# customESC.net
KiCad netlist of a schematic drawn in EAGLE
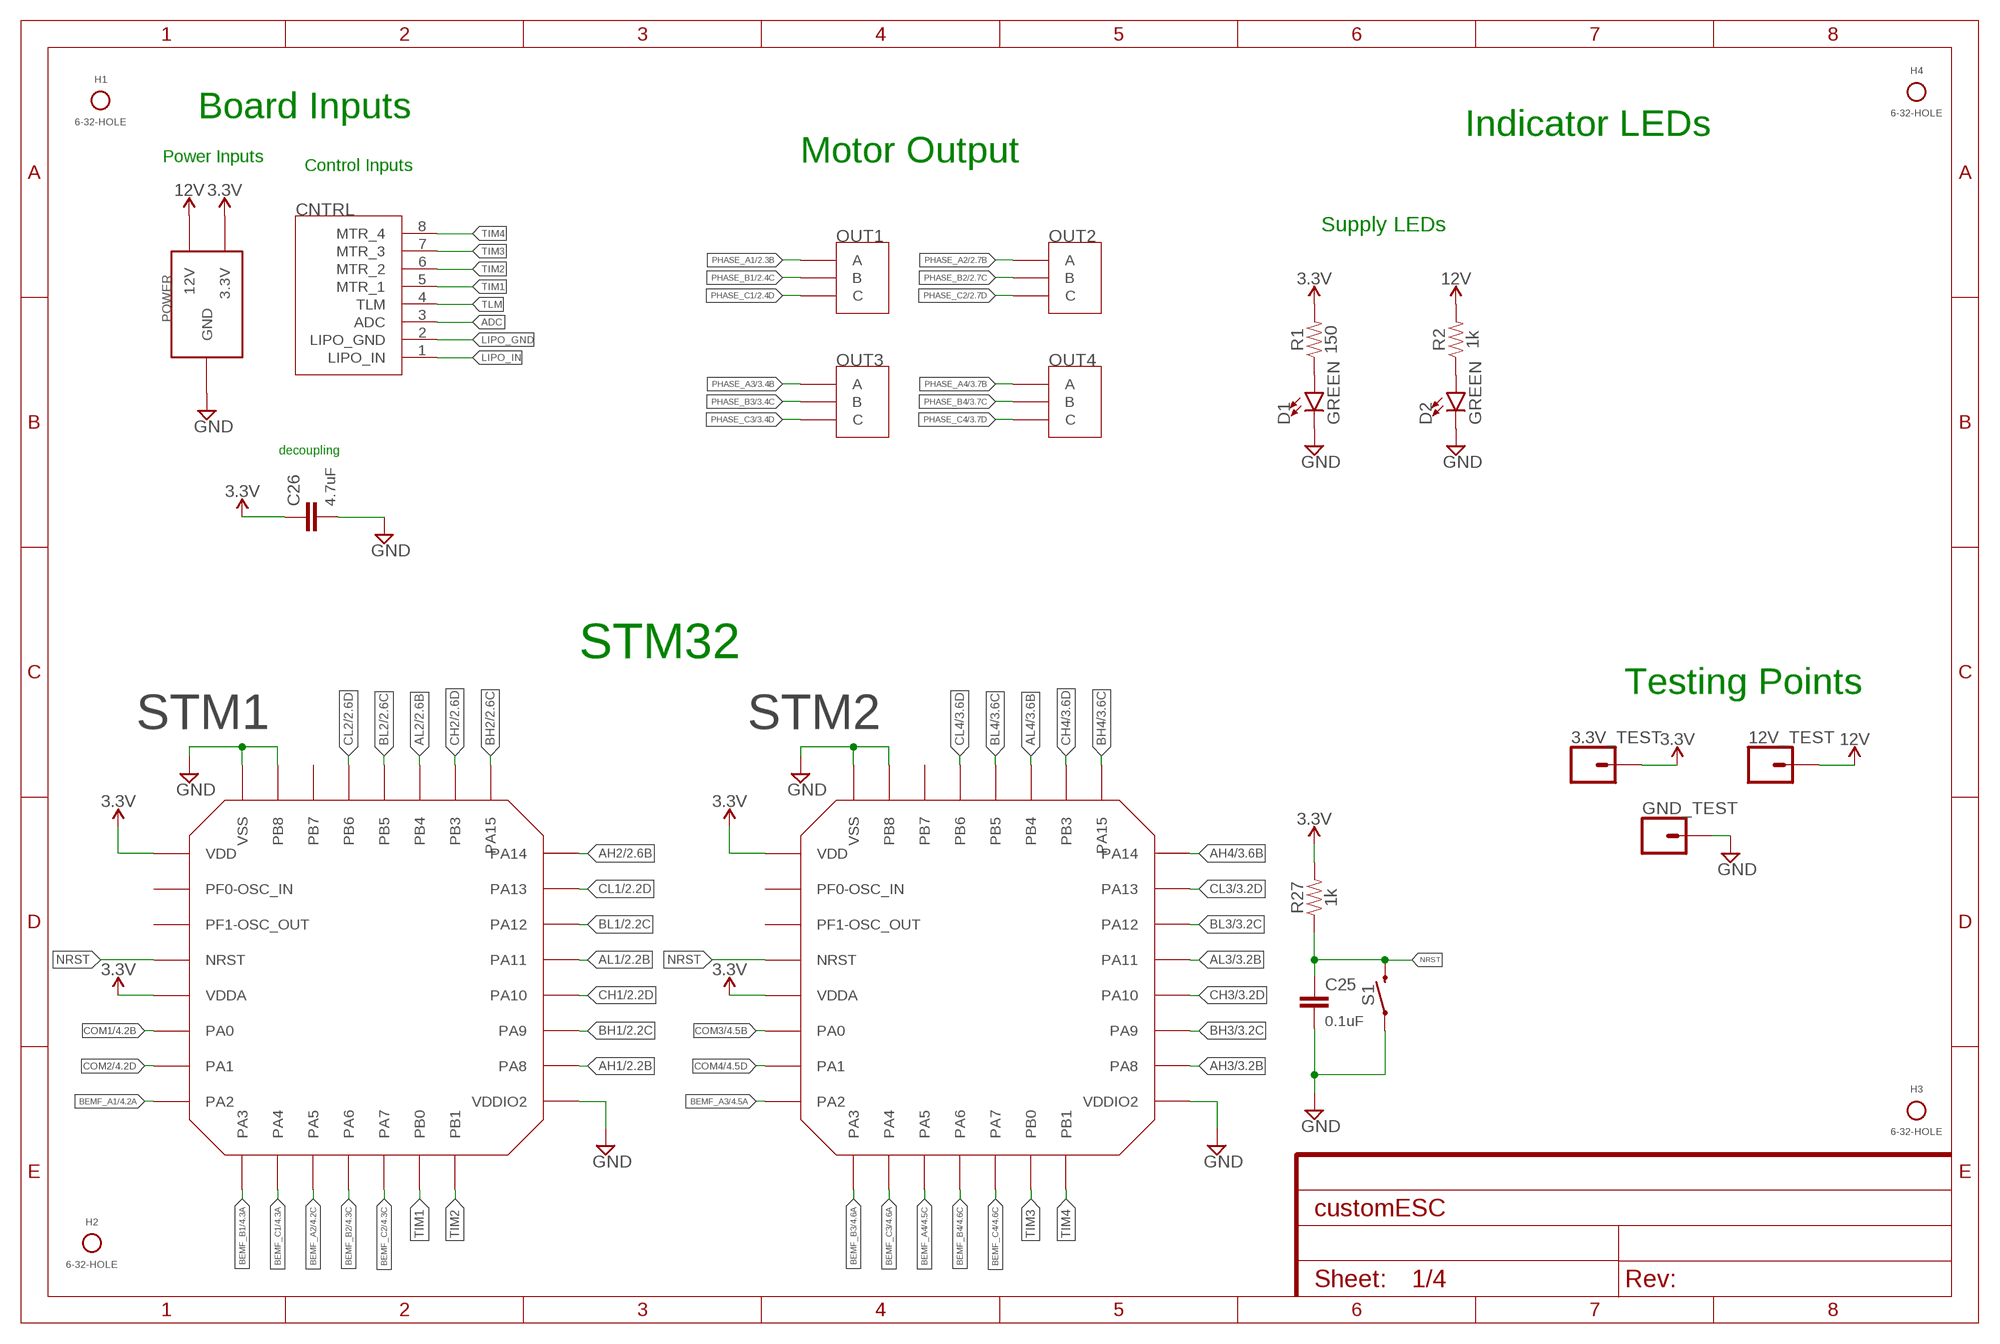
[diagram p0: schematic, sheet 1]
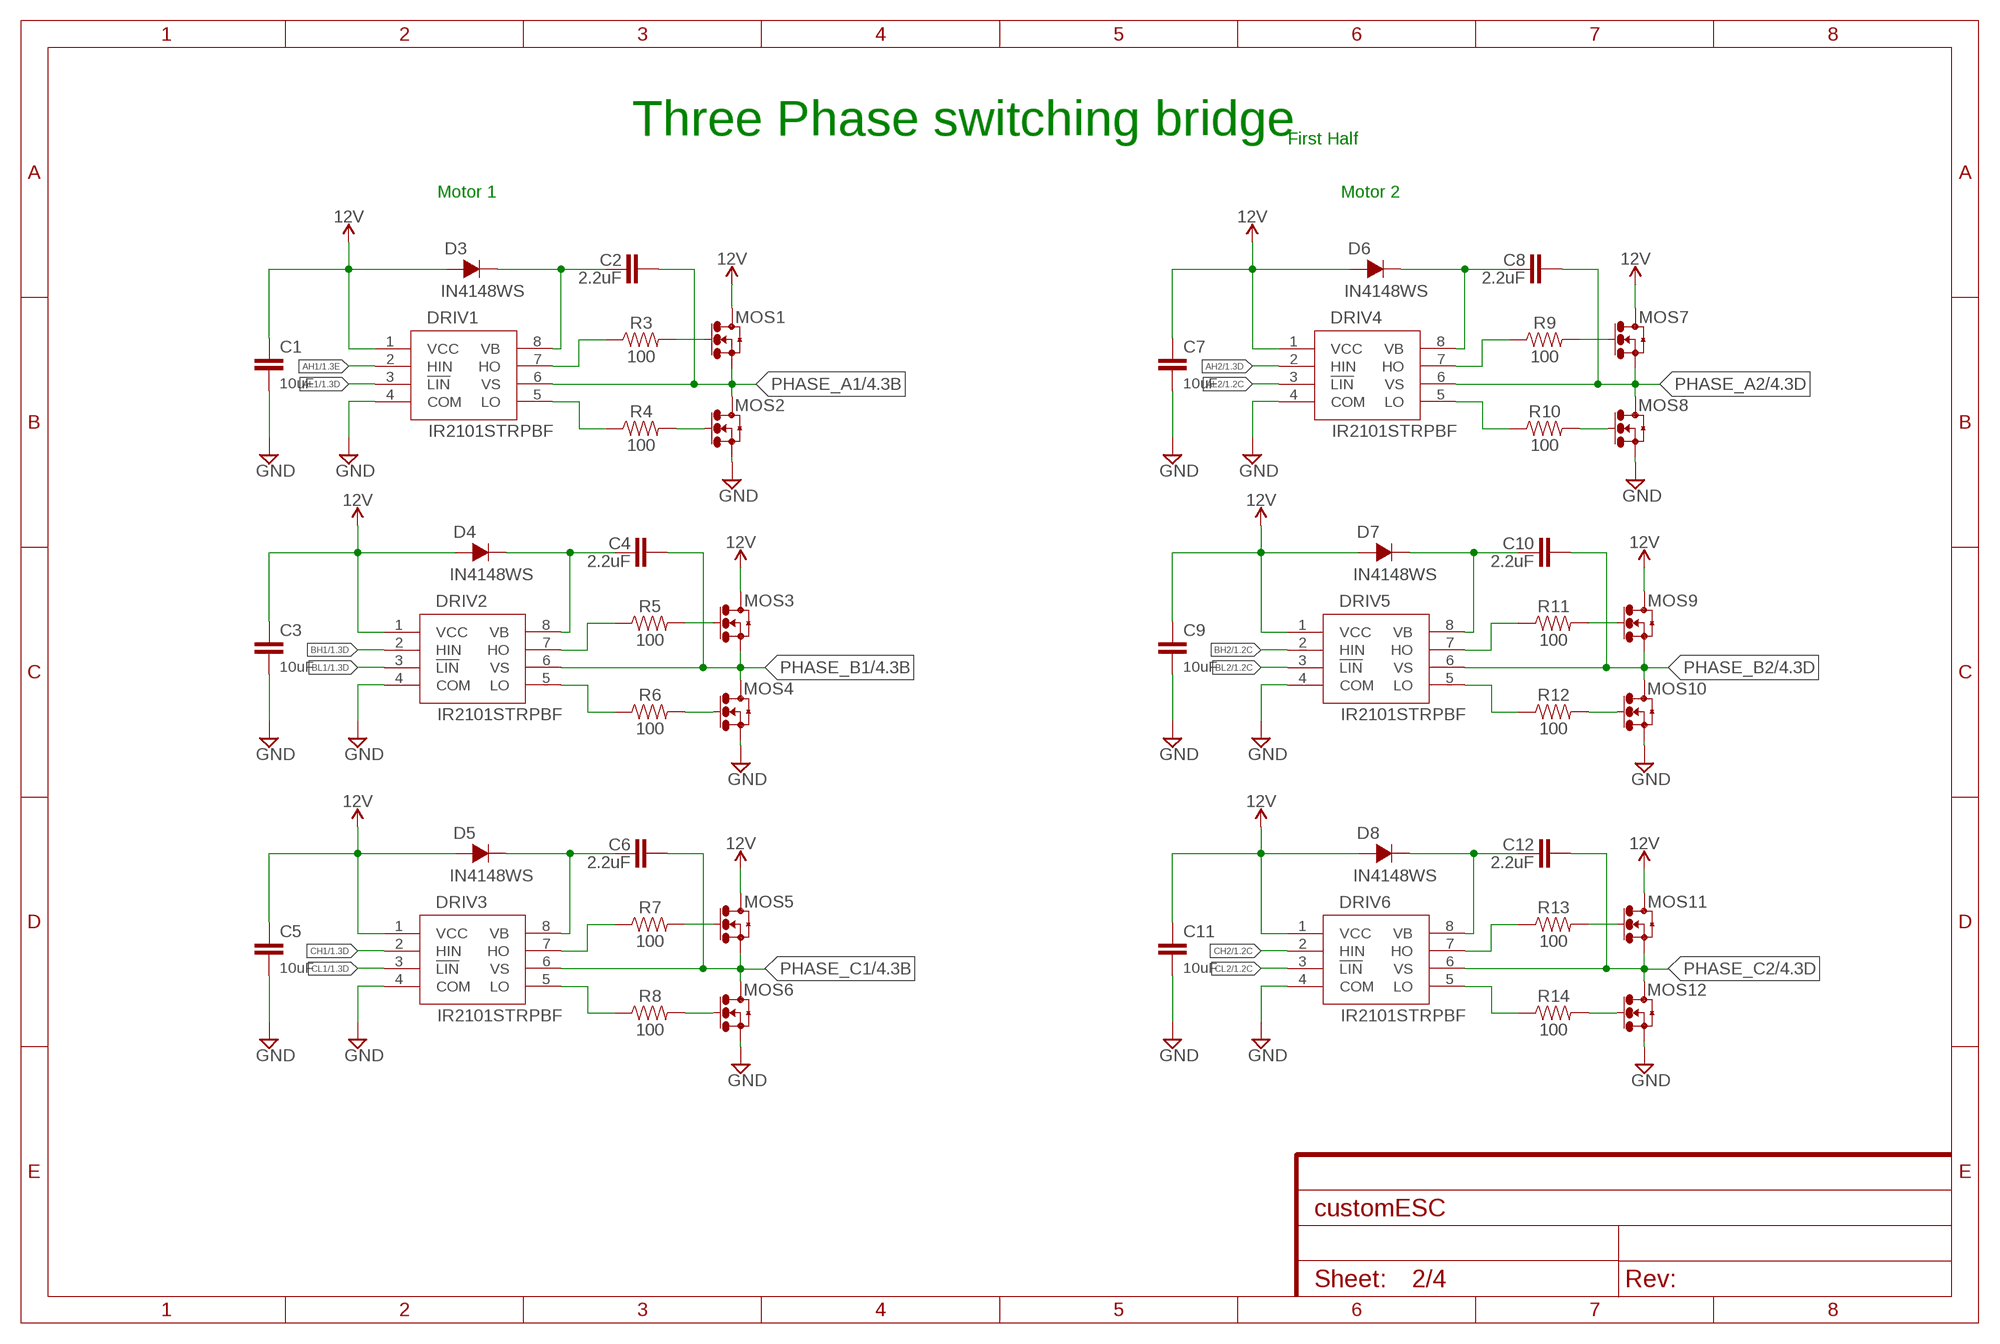
[diagram p1: schematic, sheet 2]
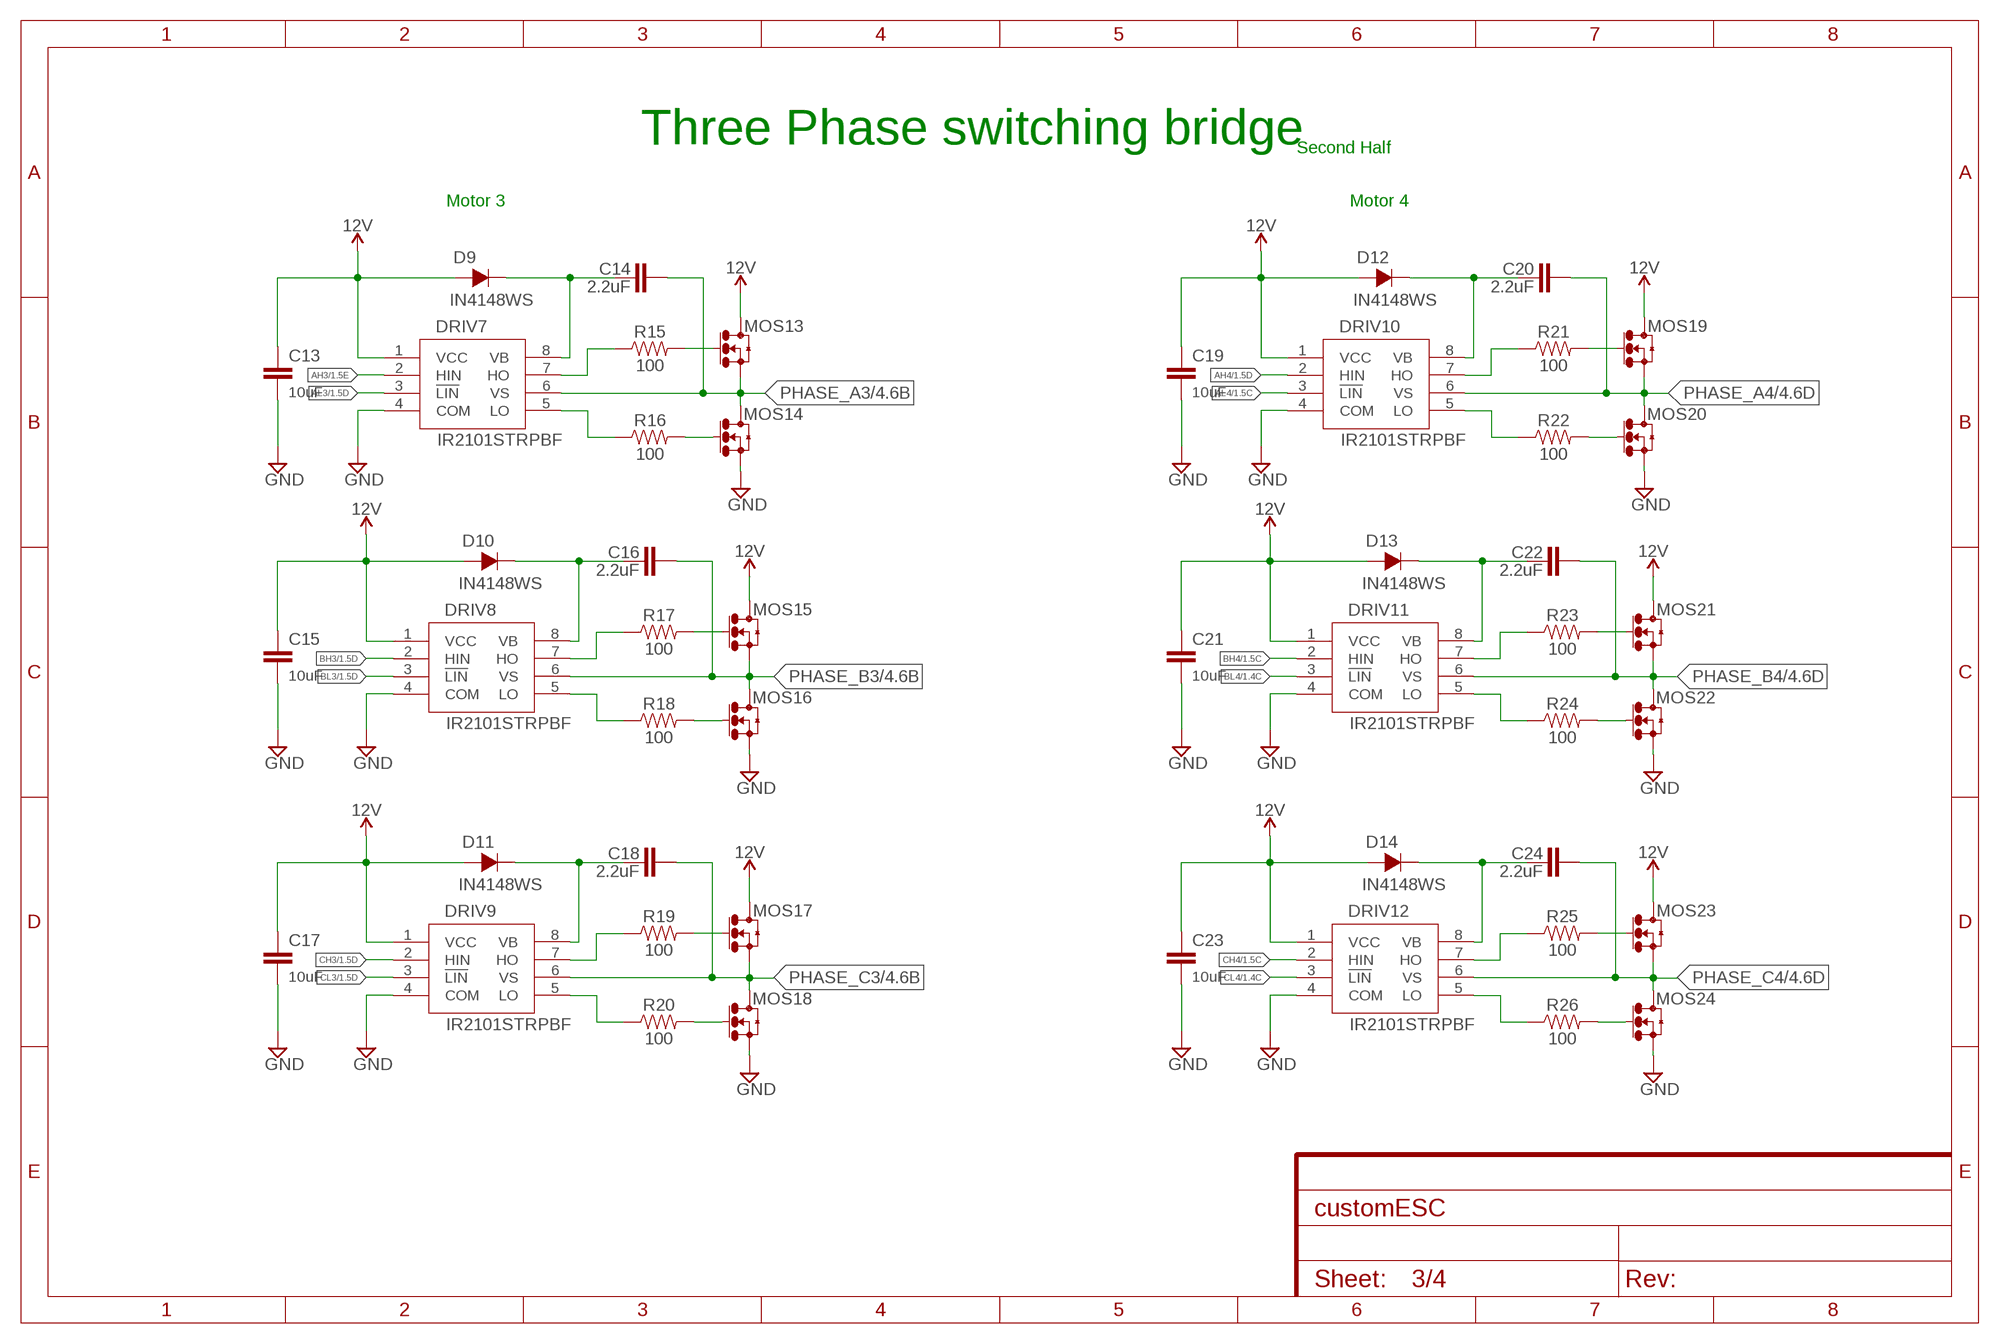
[diagram p2: schematic, sheet 3]
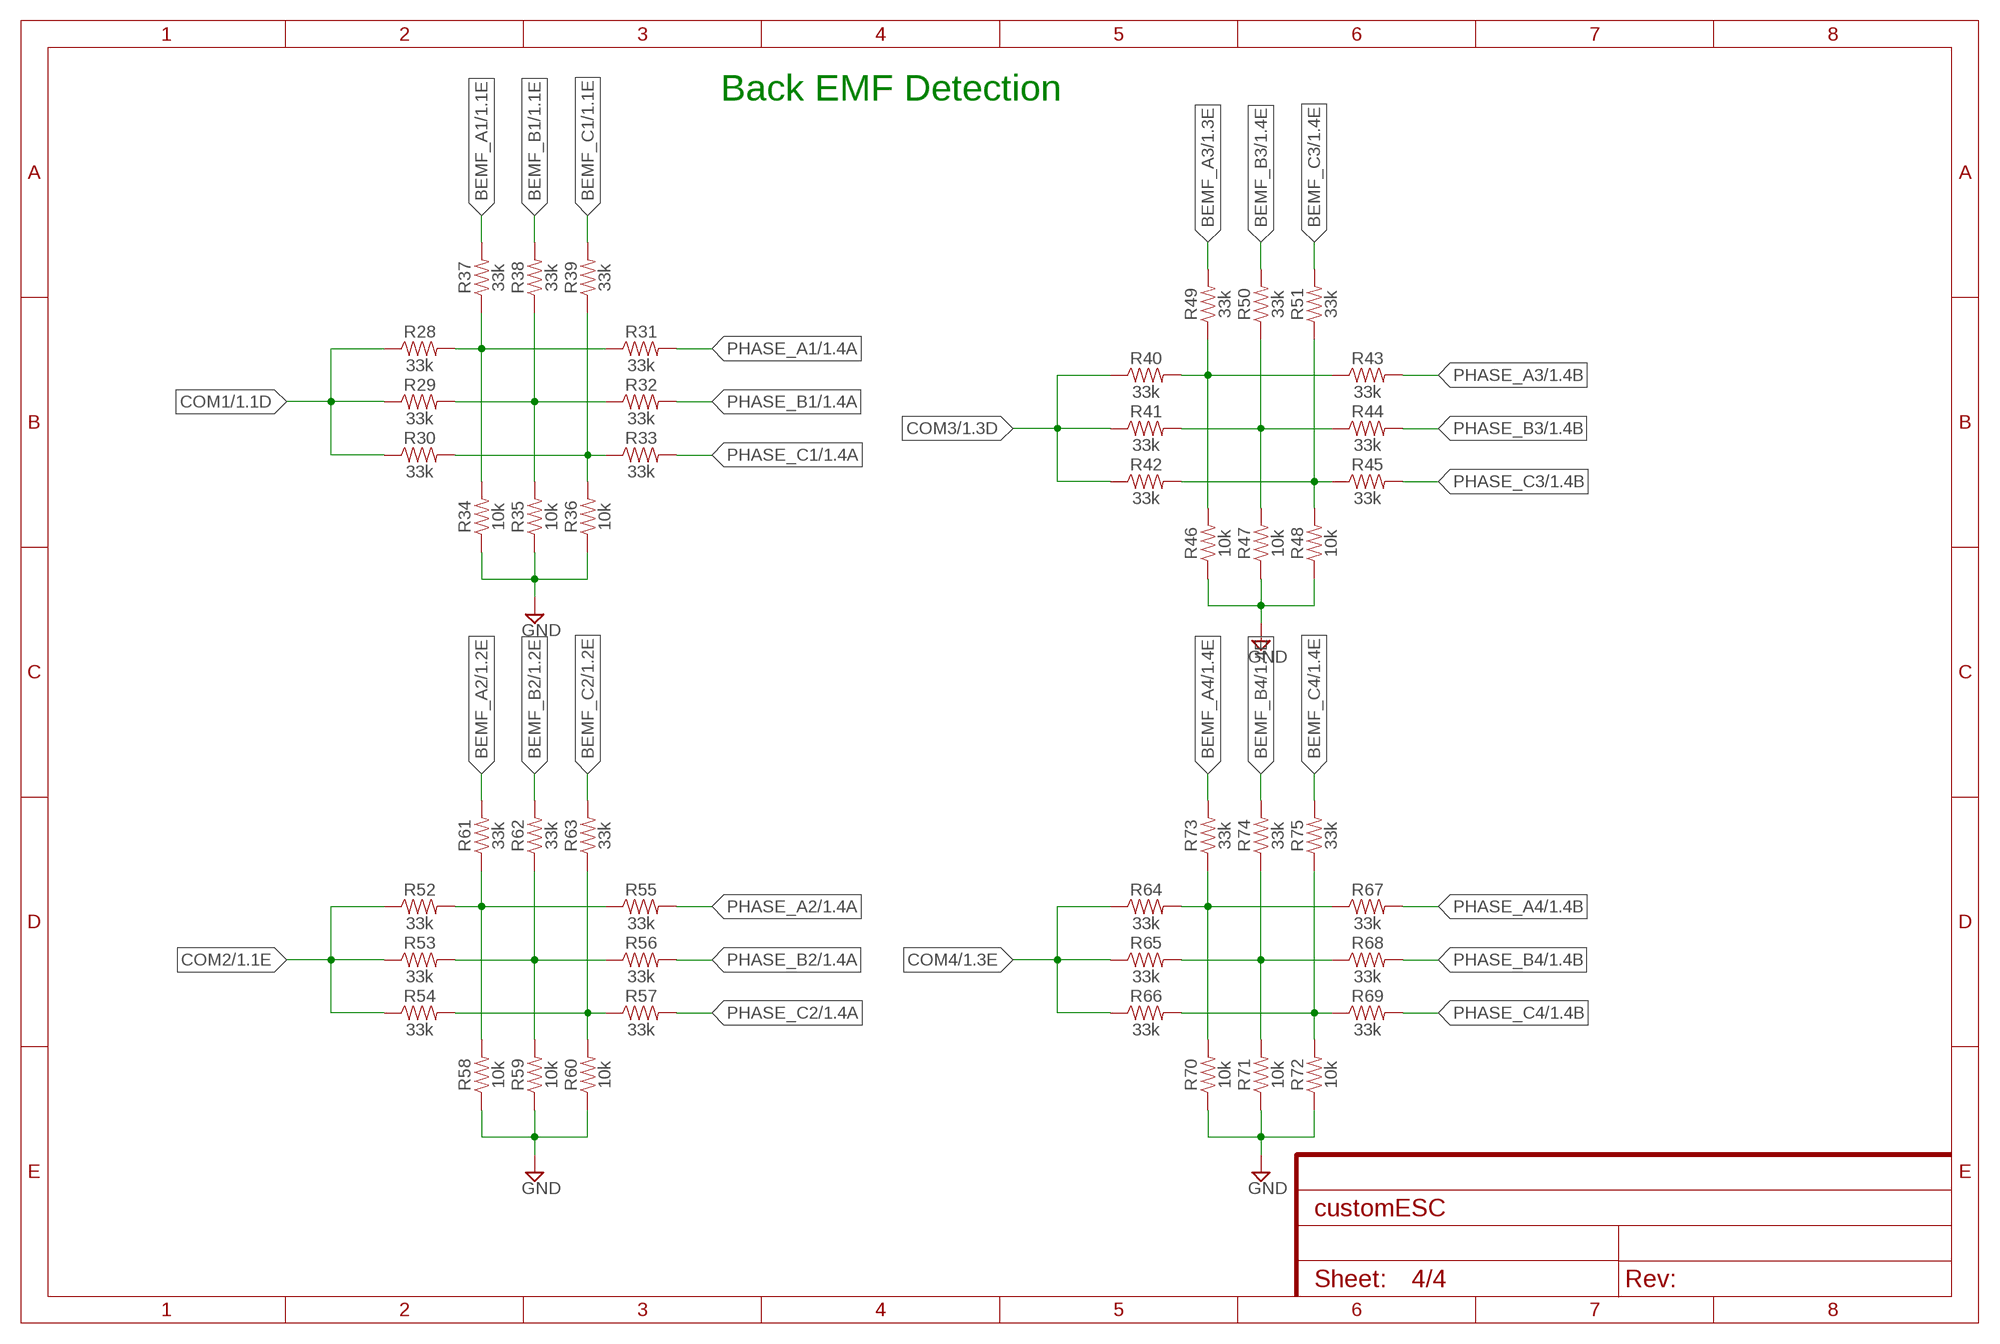
[diagram p3: schematic, sheet 4]

(export (version "E")
  (design (tool "Eeschema 10.0.6"))
  (components
    (comp (ref "R28")
      (value "33k")
      (footprint "eagle-import:0603")
      (libsource (lib "eagle-import") (part "1KOHM-0603-1/10W-1%"))
    )
    (comp (ref "R29")
      (value "33k")
      (footprint "eagle-import:0603")
      (libsource (lib "eagle-import") (part "1KOHM-0603-1/10W-1%"))
    )
    (comp (ref "R30")
      (value "33k")
      (footprint "eagle-import:0603")
      (libsource (lib "eagle-import") (part "1KOHM-0603-1/10W-1%"))
    )
    (comp (ref "R31")
      (value "33k")
      (footprint "eagle-import:0603")
      (libsource (lib "eagle-import") (part "1KOHM-0603-1/10W-1%"))
    )
    (comp (ref "R32")
      (value "33k")
      (footprint "eagle-import:0603")
      (libsource (lib "eagle-import") (part "1KOHM-0603-1/10W-1%"))
    )
    (comp (ref "R33")
      (value "33k")
      (footprint "eagle-import:0603")
      (libsource (lib "eagle-import") (part "1KOHM-0603-1/10W-1%"))
    )
    (comp (ref "R34")
      (value "10k")
      (footprint "eagle-import:0603")
      (libsource (lib "eagle-import") (part "1KOHM-0603-1/10W-1%"))
    )
    (comp (ref "R35")
      (value "10k")
      (footprint "eagle-import:0603")
      (libsource (lib "eagle-import") (part "1KOHM-0603-1/10W-1%"))
    )
    (comp (ref "R36")
      (value "10k")
      (footprint "eagle-import:0603")
      (libsource (lib "eagle-import") (part "1KOHM-0603-1/10W-1%"))
    )
    (comp (ref "R37")
      (value "33k")
      (footprint "eagle-import:0603")
      (libsource (lib "eagle-import") (part "1KOHM-0603-1/10W-1%"))
    )
    (comp (ref "R38")
      (value "33k")
      (footprint "eagle-import:0603")
      (libsource (lib "eagle-import") (part "1KOHM-0603-1/10W-1%"))
    )
    (comp (ref "R39")
      (value "33k")
      (footprint "eagle-import:0603")
      (libsource (lib "eagle-import") (part "1KOHM-0603-1/10W-1%"))
    )
    (comp (ref "R40")
      (value "33k")
      (footprint "eagle-import:0603")
      (libsource (lib "eagle-import") (part "1KOHM-0603-1/10W-1%"))
    )
    (comp (ref "R41")
      (value "33k")
      (footprint "eagle-import:0603")
      (libsource (lib "eagle-import") (part "1KOHM-0603-1/10W-1%"))
    )
    (comp (ref "R42")
      (value "33k")
      (footprint "eagle-import:0603")
      (libsource (lib "eagle-import") (part "1KOHM-0603-1/10W-1%"))
    )
    (comp (ref "R43")
      (value "33k")
      (footprint "eagle-import:0603")
      (libsource (lib "eagle-import") (part "1KOHM-0603-1/10W-1%"))
    )
    (comp (ref "R44")
      (value "33k")
      (footprint "eagle-import:0603")
      (libsource (lib "eagle-import") (part "1KOHM-0603-1/10W-1%"))
    )
    (comp (ref "R45")
      (value "33k")
      (footprint "eagle-import:0603")
      (libsource (lib "eagle-import") (part "1KOHM-0603-1/10W-1%"))
    )
    (comp (ref "R46")
      (value "10k")
      (footprint "eagle-import:0603")
      (libsource (lib "eagle-import") (part "1KOHM-0603-1/10W-1%"))
    )
    (comp (ref "R47")
      (value "10k")
      (footprint "eagle-import:0603")
      (libsource (lib "eagle-import") (part "1KOHM-0603-1/10W-1%"))
    )
    (comp (ref "R48")
      (value "10k")
      (footprint "eagle-import:0603")
      (libsource (lib "eagle-import") (part "1KOHM-0603-1/10W-1%"))
    )
    (comp (ref "R49")
      (value "33k")
      (footprint "eagle-import:0603")
      (libsource (lib "eagle-import") (part "1KOHM-0603-1/10W-1%"))
    )
    (comp (ref "R50")
      (value "33k")
      (footprint "eagle-import:0603")
      (libsource (lib "eagle-import") (part "1KOHM-0603-1/10W-1%"))
    )
    (comp (ref "R51")
      (value "33k")
      (footprint "eagle-import:0603")
      (libsource (lib "eagle-import") (part "1KOHM-0603-1/10W-1%"))
    )
    (comp (ref "R52")
      (value "33k")
      (footprint "eagle-import:0603")
      (libsource (lib "eagle-import") (part "1KOHM-0603-1/10W-1%"))
    )
    (comp (ref "R53")
      (value "33k")
      (footprint "eagle-import:0603")
      (libsource (lib "eagle-import") (part "1KOHM-0603-1/10W-1%"))
    )
    (comp (ref "R54")
      (value "33k")
      (footprint "eagle-import:0603")
      (libsource (lib "eagle-import") (part "1KOHM-0603-1/10W-1%"))
    )
    (comp (ref "R55")
      (value "33k")
      (footprint "eagle-import:0603")
      (libsource (lib "eagle-import") (part "1KOHM-0603-1/10W-1%"))
    )
    (comp (ref "R56")
      (value "33k")
      (footprint "eagle-import:0603")
      (libsource (lib "eagle-import") (part "1KOHM-0603-1/10W-1%"))
    )
    (comp (ref "R57")
      (value "33k")
      (footprint "eagle-import:0603")
      (libsource (lib "eagle-import") (part "1KOHM-0603-1/10W-1%"))
    )
    (comp (ref "R58")
      (value "10k")
      (footprint "eagle-import:0603")
      (libsource (lib "eagle-import") (part "1KOHM-0603-1/10W-1%"))
    )
    (comp (ref "R59")
      (value "10k")
      (footprint "eagle-import:0603")
      (libsource (lib "eagle-import") (part "1KOHM-0603-1/10W-1%"))
    )
    (comp (ref "R60")
      (value "10k")
      (footprint "eagle-import:0603")
      (libsource (lib "eagle-import") (part "1KOHM-0603-1/10W-1%"))
    )
    (comp (ref "R61")
      (value "33k")
      (footprint "eagle-import:0603")
      (libsource (lib "eagle-import") (part "1KOHM-0603-1/10W-1%"))
    )
    (comp (ref "R62")
      (value "33k")
      (footprint "eagle-import:0603")
      (libsource (lib "eagle-import") (part "1KOHM-0603-1/10W-1%"))
    )
    (comp (ref "R63")
      (value "33k")
      (footprint "eagle-import:0603")
      (libsource (lib "eagle-import") (part "1KOHM-0603-1/10W-1%"))
    )
    (comp (ref "R64")
      (value "33k")
      (footprint "eagle-import:0603")
      (libsource (lib "eagle-import") (part "1KOHM-0603-1/10W-1%"))
    )
    (comp (ref "R65")
      (value "33k")
      (footprint "eagle-import:0603")
      (libsource (lib "eagle-import") (part "1KOHM-0603-1/10W-1%"))
    )
    (comp (ref "R66")
      (value "33k")
      (footprint "eagle-import:0603")
      (libsource (lib "eagle-import") (part "1KOHM-0603-1/10W-1%"))
    )
    (comp (ref "R67")
      (value "33k")
      (footprint "eagle-import:0603")
      (libsource (lib "eagle-import") (part "1KOHM-0603-1/10W-1%"))
    )
    (comp (ref "R68")
      (value "33k")
      (footprint "eagle-import:0603")
      (libsource (lib "eagle-import") (part "1KOHM-0603-1/10W-1%"))
    )
    (comp (ref "R69")
      (value "33k")
      (footprint "eagle-import:0603")
      (libsource (lib "eagle-import") (part "1KOHM-0603-1/10W-1%"))
    )
    (comp (ref "R70")
      (value "10k")
      (footprint "eagle-import:0603")
      (libsource (lib "eagle-import") (part "1KOHM-0603-1/10W-1%"))
    )
    (comp (ref "R71")
      (value "10k")
      (footprint "eagle-import:0603")
      (libsource (lib "eagle-import") (part "1KOHM-0603-1/10W-1%"))
    )
    (comp (ref "R72")
      (value "10k")
      (footprint "eagle-import:0603")
      (libsource (lib "eagle-import") (part "1KOHM-0603-1/10W-1%"))
    )
    (comp (ref "R73")
      (value "33k")
      (footprint "eagle-import:0603")
      (libsource (lib "eagle-import") (part "1KOHM-0603-1/10W-1%"))
    )
    (comp (ref "R74")
      (value "33k")
      (footprint "eagle-import:0603")
      (libsource (lib "eagle-import") (part "1KOHM-0603-1/10W-1%"))
    )
    (comp (ref "R75")
      (value "33k")
      (footprint "eagle-import:0603")
      (libsource (lib "eagle-import") (part "1KOHM-0603-1/10W-1%"))
    )
    (comp (ref "3.3V_TEST")
      (value "CONN_01")
      (footprint "eagle-import:1X01")
      (libsource (lib "eagle-import") (part "CONN_01"))
    )
    (comp (ref "12V_TEST")
      (value "CONN_01")
      (footprint "eagle-import:1X01")
      (libsource (lib "eagle-import") (part "CONN_01"))
    )
    (comp (ref "C25")
      (value "0.1uF")
      (footprint "eagle-import:0603")
      (libsource (lib "eagle-import") (part "10UF-0603-6.3V-20%"))
    )
    (comp (ref "C26")
      (value "4.7uF")
      (footprint "eagle-import:0603")
      (libsource (lib "eagle-import") (part "10UF-0603-6.3V-20%"))
    )
    (comp (ref "CNTRL")
      (value "JST_8_PIN")
      (footprint "eagle-import:JST_8_PIN")
      (libsource (lib "eagle-import") (part "JST_8_PIN"))
    )
    (comp (ref "D1")
      (value "GREEN")
      (footprint "eagle-import:LED-0603")
      (libsource (lib "eagle-import") (part "LED-GREEN0603"))
    )
    (comp (ref "D2")
      (value "GREEN")
      (footprint "eagle-import:LED-0603")
      (libsource (lib "eagle-import") (part "LED-GREEN0603"))
    )
    (comp (ref "GND_TEST")
      (value "CONN_01")
      (footprint "eagle-import:1X01")
      (libsource (lib "eagle-import") (part "CONN_01"))
    )
    (comp (ref "H1")
      (value "6-32-HOLE")
      (footprint "eagle-import:MOUNTING_HOLE")
      (libsource (lib "eagle-import") (part "6-32-HOLE"))
    )
    (comp (ref "H2")
      (value "6-32-HOLE")
      (footprint "eagle-import:MOUNTING_HOLE")
      (libsource (lib "eagle-import") (part "6-32-HOLE"))
    )
    (comp (ref "H3")
      (value "6-32-HOLE")
      (footprint "eagle-import:MOUNTING_HOLE")
      (libsource (lib "eagle-import") (part "6-32-HOLE"))
    )
    (comp (ref "H4")
      (value "6-32-HOLE")
      (footprint "eagle-import:MOUNTING_HOLE")
      (libsource (lib "eagle-import") (part "6-32-HOLE"))
    )
    (comp (ref "OUT1")
      (value "IPBT-103-H1-T-S")
      (footprint "eagle-import:IPBT-103-H1-T-S")
      (libsource (lib "eagle-import") (part "IPBT-103-H1-T-S"))
    )
    (comp (ref "OUT2")
      (value "IPBT-103-H1-T-S")
      (footprint "eagle-import:IPBT-103-H1-T-S")
      (libsource (lib "eagle-import") (part "IPBT-103-H1-T-S"))
    )
    (comp (ref "OUT3")
      (value "IPBT-103-H1-T-S")
      (footprint "eagle-import:IPBT-103-H1-T-S")
      (libsource (lib "eagle-import") (part "IPBT-103-H1-T-S"))
    )
    (comp (ref "OUT4")
      (value "IPBT-103-H1-T-S")
      (footprint "eagle-import:IPBT-103-H1-T-S")
      (libsource (lib "eagle-import") (part "IPBT-103-H1-T-S"))
    )
    (comp (ref "POWER")
      (value "12V-CONNECTOR")
      (footprint "eagle-import:12V-CONNECTOR")
      (libsource (lib "eagle-import") (part "12V-CONNECTOR"))
    )
    (comp (ref "R1")
      (value "150")
      (footprint "eagle-import:0603")
      (libsource (lib "eagle-import") (part "1KOHM-0603-1/10W-1%"))
    )
    (comp (ref "R2")
      (value "1k")
      (footprint "eagle-import:0603")
      (libsource (lib "eagle-import") (part "1KOHM-0603-1/10W-1%"))
    )
    (comp (ref "R27")
      (value "1k")
      (footprint "eagle-import:0603")
      (libsource (lib "eagle-import") (part "1KOHM-0603-1/10W-1%"))
    )
    (comp (ref "S1")
      (value "MOMENTARY-SWITCH-SPST-SMD-6.0X3.5MM")
      (footprint "eagle-import:TACTILE_SWITCH_SMD_6.0X3.5MM")
      (libsource (lib "eagle-import") (part "MOMENTARY-SWITCH-SPST-SMD-6.0X3.5MM"))
    )
    (comp (ref "STM1")
      (value "STM32F042K6T6")
      (footprint "eagle-import:STM32F042K6T6")
      (libsource (lib "eagle-import") (part "STM32F042K6T6"))
    )
    (comp (ref "STM2")
      (value "STM32F042K6T6")
      (footprint "eagle-import:STM32F042K6T6")
      (libsource (lib "eagle-import") (part "STM32F042K6T6"))
    )
    (comp (ref "C13")
      (value "10uF")
      (footprint "eagle-import:0603")
      (libsource (lib "eagle-import") (part "10UF-0603-6.3V-20%"))
    )
    (comp (ref "C14")
      (value "2.2uF")
      (footprint "eagle-import:0603")
      (libsource (lib "eagle-import") (part "10UF-0603-6.3V-20%"))
    )
    (comp (ref "C15")
      (value "10uF")
      (footprint "eagle-import:0603")
      (libsource (lib "eagle-import") (part "10UF-0603-6.3V-20%"))
    )
    (comp (ref "C16")
      (value "2.2uF")
      (footprint "eagle-import:0603")
      (libsource (lib "eagle-import") (part "10UF-0603-6.3V-20%"))
    )
    (comp (ref "C17")
      (value "10uF")
      (footprint "eagle-import:0603")
      (libsource (lib "eagle-import") (part "10UF-0603-6.3V-20%"))
    )
    (comp (ref "C18")
      (value "2.2uF")
      (footprint "eagle-import:0603")
      (libsource (lib "eagle-import") (part "10UF-0603-6.3V-20%"))
    )
    (comp (ref "C19")
      (value "10uF")
      (footprint "eagle-import:0603")
      (libsource (lib "eagle-import") (part "10UF-0603-6.3V-20%"))
    )
    (comp (ref "C20")
      (value "2.2uF")
      (footprint "eagle-import:0603")
      (libsource (lib "eagle-import") (part "10UF-0603-6.3V-20%"))
    )
    (comp (ref "C21")
      (value "10uF")
      (footprint "eagle-import:0603")
      (libsource (lib "eagle-import") (part "10UF-0603-6.3V-20%"))
    )
    (comp (ref "C22")
      (value "2.2uF")
      (footprint "eagle-import:0603")
      (libsource (lib "eagle-import") (part "10UF-0603-6.3V-20%"))
    )
    (comp (ref "C23")
      (value "10uF")
      (footprint "eagle-import:0603")
      (libsource (lib "eagle-import") (part "10UF-0603-6.3V-20%"))
    )
    (comp (ref "C24")
      (value "2.2uF")
      (footprint "eagle-import:0603")
      (libsource (lib "eagle-import") (part "10UF-0603-6.3V-20%"))
    )
    (comp (ref "D9")
      (value "IN4148WS")
      (footprint "eagle-import:IN4148WS")
      (libsource (lib "eagle-import") (part "IN4148WS"))
    )
    (comp (ref "D10")
      (value "IN4148WS")
      (footprint "eagle-import:IN4148WS")
      (libsource (lib "eagle-import") (part "IN4148WS"))
    )
    (comp (ref "D11")
      (value "IN4148WS")
      (footprint "eagle-import:IN4148WS")
      (libsource (lib "eagle-import") (part "IN4148WS"))
    )
    (comp (ref "D12")
      (value "IN4148WS")
      (footprint "eagle-import:IN4148WS")
      (libsource (lib "eagle-import") (part "IN4148WS"))
    )
    (comp (ref "D13")
      (value "IN4148WS")
      (footprint "eagle-import:IN4148WS")
      (libsource (lib "eagle-import") (part "IN4148WS"))
    )
    (comp (ref "D14")
      (value "IN4148WS")
      (footprint "eagle-import:IN4148WS")
      (libsource (lib "eagle-import") (part "IN4148WS"))
    )
    (comp (ref "DRIV7")
      (value "IR2101STRPBF")
      (footprint "eagle-import:IR2101STRPBF")
      (libsource (lib "eagle-import") (part "IR2101STRPBF"))
    )
    (comp (ref "DRIV8")
      (value "IR2101STRPBF")
      (footprint "eagle-import:IR2101STRPBF")
      (libsource (lib "eagle-import") (part "IR2101STRPBF"))
    )
    (comp (ref "DRIV9")
      (value "IR2101STRPBF")
      (footprint "eagle-import:IR2101STRPBF")
      (libsource (lib "eagle-import") (part "IR2101STRPBF"))
    )
    (comp (ref "DRIV10")
      (value "IR2101STRPBF")
      (footprint "eagle-import:IR2101STRPBF")
      (libsource (lib "eagle-import") (part "IR2101STRPBF"))
    )
    (comp (ref "DRIV11")
      (value "IR2101STRPBF")
      (footprint "eagle-import:IR2101STRPBF")
      (libsource (lib "eagle-import") (part "IR2101STRPBF"))
    )
    (comp (ref "DRIV12")
      (value "IR2101STRPBF")
      (footprint "eagle-import:IR2101STRPBF")
      (libsource (lib "eagle-import") (part "IR2101STRPBF"))
    )
    (comp (ref "MOS13")
      (value "IRLR7843TRPBF")
      (footprint "eagle-import:IRLR7843TRPBF")
      (libsource (lib "eagle-import") (part "IRLR7843TRPBF"))
    )
    (comp (ref "MOS14")
      (value "IRLR7843TRPBF")
      (footprint "eagle-import:IRLR7843TRPBF")
      (libsource (lib "eagle-import") (part "IRLR7843TRPBF"))
    )
    (comp (ref "MOS15")
      (value "IRLR7843TRPBF")
      (footprint "eagle-import:IRLR7843TRPBF")
      (libsource (lib "eagle-import") (part "IRLR7843TRPBF"))
    )
    (comp (ref "MOS16")
      (value "IRLR7843TRPBF")
      (footprint "eagle-import:IRLR7843TRPBF")
      (libsource (lib "eagle-import") (part "IRLR7843TRPBF"))
    )
    (comp (ref "MOS17")
      (value "IRLR7843TRPBF")
      (footprint "eagle-import:IRLR7843TRPBF")
      (libsource (lib "eagle-import") (part "IRLR7843TRPBF"))
    )
    (comp (ref "MOS18")
      (value "IRLR7843TRPBF")
      (footprint "eagle-import:IRLR7843TRPBF")
      (libsource (lib "eagle-import") (part "IRLR7843TRPBF"))
    )
    (comp (ref "MOS19")
      (value "IRLR7843TRPBF")
      (footprint "eagle-import:IRLR7843TRPBF")
      (libsource (lib "eagle-import") (part "IRLR7843TRPBF"))
    )
    (comp (ref "MOS20")
      (value "IRLR7843TRPBF")
      (footprint "eagle-import:IRLR7843TRPBF")
      (libsource (lib "eagle-import") (part "IRLR7843TRPBF"))
    )
    (comp (ref "MOS21")
      (value "IRLR7843TRPBF")
      (footprint "eagle-import:IRLR7843TRPBF")
      (libsource (lib "eagle-import") (part "IRLR7843TRPBF"))
    )
    (comp (ref "MOS22")
      (value "IRLR7843TRPBF")
      (footprint "eagle-import:IRLR7843TRPBF")
      (libsource (lib "eagle-import") (part "IRLR7843TRPBF"))
    )
    (comp (ref "MOS23")
      (value "IRLR7843TRPBF")
      (footprint "eagle-import:IRLR7843TRPBF")
      (libsource (lib "eagle-import") (part "IRLR7843TRPBF"))
    )
    (comp (ref "MOS24")
      (value "IRLR7843TRPBF")
      (footprint "eagle-import:IRLR7843TRPBF")
      (libsource (lib "eagle-import") (part "IRLR7843TRPBF"))
    )
    (comp (ref "R15")
      (value "100")
      (footprint "eagle-import:0603")
      (libsource (lib "eagle-import") (part "1KOHM-0603-1/10W-1%"))
    )
    (comp (ref "R16")
      (value "100")
      (footprint "eagle-import:0603")
      (libsource (lib "eagle-import") (part "1KOHM-0603-1/10W-1%"))
    )
    (comp (ref "R17")
      (value "100")
      (footprint "eagle-import:0603")
      (libsource (lib "eagle-import") (part "1KOHM-0603-1/10W-1%"))
    )
    (comp (ref "R18")
      (value "100")
      (footprint "eagle-import:0603")
      (libsource (lib "eagle-import") (part "1KOHM-0603-1/10W-1%"))
    )
    (comp (ref "R19")
      (value "100")
      (footprint "eagle-import:0603")
      (libsource (lib "eagle-import") (part "1KOHM-0603-1/10W-1%"))
    )
    (comp (ref "R20")
      (value "100")
      (footprint "eagle-import:0603")
      (libsource (lib "eagle-import") (part "1KOHM-0603-1/10W-1%"))
    )
    (comp (ref "R21")
      (value "100")
      (footprint "eagle-import:0603")
      (libsource (lib "eagle-import") (part "1KOHM-0603-1/10W-1%"))
    )
    (comp (ref "R22")
      (value "100")
      (footprint "eagle-import:0603")
      (libsource (lib "eagle-import") (part "1KOHM-0603-1/10W-1%"))
    )
    (comp (ref "R23")
      (value "100")
      (footprint "eagle-import:0603")
      (libsource (lib "eagle-import") (part "1KOHM-0603-1/10W-1%"))
    )
    (comp (ref "R24")
      (value "100")
      (footprint "eagle-import:0603")
      (libsource (lib "eagle-import") (part "1KOHM-0603-1/10W-1%"))
    )
    (comp (ref "R25")
      (value "100")
      (footprint "eagle-import:0603")
      (libsource (lib "eagle-import") (part "1KOHM-0603-1/10W-1%"))
    )
    (comp (ref "R26")
      (value "100")
      (footprint "eagle-import:0603")
      (libsource (lib "eagle-import") (part "1KOHM-0603-1/10W-1%"))
    )
    (comp (ref "C1")
      (value "10uF")
      (footprint "eagle-import:0603")
      (libsource (lib "eagle-import") (part "10UF-0603-6.3V-20%"))
    )
    (comp (ref "C2")
      (value "2.2uF")
      (footprint "eagle-import:0603")
      (libsource (lib "eagle-import") (part "10UF-0603-6.3V-20%"))
    )
    (comp (ref "C3")
      (value "10uF")
      (footprint "eagle-import:0603")
      (libsource (lib "eagle-import") (part "10UF-0603-6.3V-20%"))
    )
    (comp (ref "C4")
      (value "2.2uF")
      (footprint "eagle-import:0603")
      (libsource (lib "eagle-import") (part "10UF-0603-6.3V-20%"))
    )
    (comp (ref "C5")
      (value "10uF")
      (footprint "eagle-import:0603")
      (libsource (lib "eagle-import") (part "10UF-0603-6.3V-20%"))
    )
    (comp (ref "C6")
      (value "2.2uF")
      (footprint "eagle-import:0603")
      (libsource (lib "eagle-import") (part "10UF-0603-6.3V-20%"))
    )
    (comp (ref "C7")
      (value "10uF")
      (footprint "eagle-import:0603")
      (libsource (lib "eagle-import") (part "10UF-0603-6.3V-20%"))
    )
    (comp (ref "C8")
      (value "2.2uF")
      (footprint "eagle-import:0603")
      (libsource (lib "eagle-import") (part "10UF-0603-6.3V-20%"))
    )
    (comp (ref "C9")
      (value "10uF")
      (footprint "eagle-import:0603")
      (libsource (lib "eagle-import") (part "10UF-0603-6.3V-20%"))
    )
    (comp (ref "C10")
      (value "2.2uF")
      (footprint "eagle-import:0603")
      (libsource (lib "eagle-import") (part "10UF-0603-6.3V-20%"))
    )
    (comp (ref "C11")
      (value "10uF")
      (footprint "eagle-import:0603")
      (libsource (lib "eagle-import") (part "10UF-0603-6.3V-20%"))
    )
    (comp (ref "C12")
      (value "2.2uF")
      (footprint "eagle-import:0603")
      (libsource (lib "eagle-import") (part "10UF-0603-6.3V-20%"))
    )
    (comp (ref "D3")
      (value "IN4148WS")
      (footprint "eagle-import:IN4148WS")
      (libsource (lib "eagle-import") (part "IN4148WS"))
    )
    (comp (ref "D4")
      (value "IN4148WS")
      (footprint "eagle-import:IN4148WS")
      (libsource (lib "eagle-import") (part "IN4148WS"))
    )
    (comp (ref "D5")
      (value "IN4148WS")
      (footprint "eagle-import:IN4148WS")
      (libsource (lib "eagle-import") (part "IN4148WS"))
    )
    (comp (ref "D6")
      (value "IN4148WS")
      (footprint "eagle-import:IN4148WS")
      (libsource (lib "eagle-import") (part "IN4148WS"))
    )
    (comp (ref "D7")
      (value "IN4148WS")
      (footprint "eagle-import:IN4148WS")
      (libsource (lib "eagle-import") (part "IN4148WS"))
    )
    (comp (ref "D8")
      (value "IN4148WS")
      (footprint "eagle-import:IN4148WS")
      (libsource (lib "eagle-import") (part "IN4148WS"))
    )
    (comp (ref "DRIV1")
      (value "IR2101STRPBF")
      (footprint "eagle-import:IR2101STRPBF")
      (libsource (lib "eagle-import") (part "IR2101STRPBF"))
    )
    (comp (ref "DRIV2")
      (value "IR2101STRPBF")
      (footprint "eagle-import:IR2101STRPBF")
      (libsource (lib "eagle-import") (part "IR2101STRPBF"))
    )
    (comp (ref "DRIV3")
      (value "IR2101STRPBF")
      (footprint "eagle-import:IR2101STRPBF")
      (libsource (lib "eagle-import") (part "IR2101STRPBF"))
    )
    (comp (ref "DRIV4")
      (value "IR2101STRPBF")
      (footprint "eagle-import:IR2101STRPBF")
      (libsource (lib "eagle-import") (part "IR2101STRPBF"))
    )
    (comp (ref "DRIV5")
      (value "IR2101STRPBF")
      (footprint "eagle-import:IR2101STRPBF")
      (libsource (lib "eagle-import") (part "IR2101STRPBF"))
    )
    (comp (ref "DRIV6")
      (value "IR2101STRPBF")
      (footprint "eagle-import:IR2101STRPBF")
      (libsource (lib "eagle-import") (part "IR2101STRPBF"))
    )
    (comp (ref "MOS1")
      (value "IRLR7843TRPBF")
      (footprint "eagle-import:IRLR7843TRPBF")
      (libsource (lib "eagle-import") (part "IRLR7843TRPBF"))
    )
    (comp (ref "MOS2")
      (value "IRLR7843TRPBF")
      (footprint "eagle-import:IRLR7843TRPBF")
      (libsource (lib "eagle-import") (part "IRLR7843TRPBF"))
    )
    (comp (ref "MOS3")
      (value "IRLR7843TRPBF")
      (footprint "eagle-import:IRLR7843TRPBF")
      (libsource (lib "eagle-import") (part "IRLR7843TRPBF"))
    )
    (comp (ref "MOS4")
      (value "IRLR7843TRPBF")
      (footprint "eagle-import:IRLR7843TRPBF")
      (libsource (lib "eagle-import") (part "IRLR7843TRPBF"))
    )
    (comp (ref "MOS5")
      (value "IRLR7843TRPBF")
      (footprint "eagle-import:IRLR7843TRPBF")
      (libsource (lib "eagle-import") (part "IRLR7843TRPBF"))
    )
    (comp (ref "MOS6")
      (value "IRLR7843TRPBF")
      (footprint "eagle-import:IRLR7843TRPBF")
      (libsource (lib "eagle-import") (part "IRLR7843TRPBF"))
    )
    (comp (ref "MOS7")
      (value "IRLR7843TRPBF")
      (footprint "eagle-import:IRLR7843TRPBF")
      (libsource (lib "eagle-import") (part "IRLR7843TRPBF"))
    )
    (comp (ref "MOS8")
      (value "IRLR7843TRPBF")
      (footprint "eagle-import:IRLR7843TRPBF")
      (libsource (lib "eagle-import") (part "IRLR7843TRPBF"))
    )
    (comp (ref "MOS9")
      (value "IRLR7843TRPBF")
      (footprint "eagle-import:IRLR7843TRPBF")
      (libsource (lib "eagle-import") (part "IRLR7843TRPBF"))
    )
    (comp (ref "MOS10")
      (value "IRLR7843TRPBF")
      (footprint "eagle-import:IRLR7843TRPBF")
      (libsource (lib "eagle-import") (part "IRLR7843TRPBF"))
    )
    (comp (ref "MOS11")
      (value "IRLR7843TRPBF")
      (footprint "eagle-import:IRLR7843TRPBF")
      (libsource (lib "eagle-import") (part "IRLR7843TRPBF"))
    )
    (comp (ref "MOS12")
      (value "IRLR7843TRPBF")
      (footprint "eagle-import:IRLR7843TRPBF")
      (libsource (lib "eagle-import") (part "IRLR7843TRPBF"))
    )
    (comp (ref "R3")
      (value "100")
      (footprint "eagle-import:0603")
      (libsource (lib "eagle-import") (part "1KOHM-0603-1/10W-1%"))
    )
    (comp (ref "R4")
      (value "100")
      (footprint "eagle-import:0603")
      (libsource (lib "eagle-import") (part "1KOHM-0603-1/10W-1%"))
    )
    (comp (ref "R5")
      (value "100")
      (footprint "eagle-import:0603")
      (libsource (lib "eagle-import") (part "1KOHM-0603-1/10W-1%"))
    )
    (comp (ref "R6")
      (value "100")
      (footprint "eagle-import:0603")
      (libsource (lib "eagle-import") (part "1KOHM-0603-1/10W-1%"))
    )
    (comp (ref "R7")
      (value "100")
      (footprint "eagle-import:0603")
      (libsource (lib "eagle-import") (part "1KOHM-0603-1/10W-1%"))
    )
    (comp (ref "R8")
      (value "100")
      (footprint "eagle-import:0603")
      (libsource (lib "eagle-import") (part "1KOHM-0603-1/10W-1%"))
    )
    (comp (ref "R9")
      (value "100")
      (footprint "eagle-import:0603")
      (libsource (lib "eagle-import") (part "1KOHM-0603-1/10W-1%"))
    )
    (comp (ref "R10")
      (value "100")
      (footprint "eagle-import:0603")
      (libsource (lib "eagle-import") (part "1KOHM-0603-1/10W-1%"))
    )
    (comp (ref "R11")
      (value "100")
      (footprint "eagle-import:0603")
      (libsource (lib "eagle-import") (part "1KOHM-0603-1/10W-1%"))
    )
    (comp (ref "R12")
      (value "100")
      (footprint "eagle-import:0603")
      (libsource (lib "eagle-import") (part "1KOHM-0603-1/10W-1%"))
    )
    (comp (ref "R13")
      (value "100")
      (footprint "eagle-import:0603")
      (libsource (lib "eagle-import") (part "1KOHM-0603-1/10W-1%"))
    )
    (comp (ref "R14")
      (value "100")
      (footprint "eagle-import:0603")
      (libsource (lib "eagle-import") (part "1KOHM-0603-1/10W-1%"))
    )
  )
  (nets
    (net (code "1") (name "ADC") (class "Default")
      (node (ref "CNTRL") (pin "3") (pinfunction "ADC_3") (pintype "bidirectional"))
    )
    (net (code "2") (name "AH1") (class "Default")
      (node (ref "DRIV1") (pin "2") (pinfunction "HIN_2") (pintype "bidirectional"))
      (node (ref "STM1") (pin "PA8") (pinfunction "PA8_PA8") (pintype "bidirectional"))
    )
    (net (code "3") (name "AH2") (class "Default")
      (node (ref "DRIV4") (pin "2") (pinfunction "HIN_2") (pintype "bidirectional"))
      (node (ref "STM1") (pin "PA14") (pinfunction "PA14_PA14") (pintype "bidirectional"))
    )
    (net (code "4") (name "AH3") (class "Default")
      (node (ref "DRIV7") (pin "2") (pinfunction "HIN_2") (pintype "bidirectional"))
      (node (ref "STM2") (pin "PA8") (pinfunction "PA8_PA8") (pintype "bidirectional"))
    )
    (net (code "5") (name "AH4") (class "Default")
      (node (ref "DRIV10") (pin "2") (pinfunction "HIN_2") (pintype "bidirectional"))
      (node (ref "STM2") (pin "PA14") (pinfunction "PA14_PA14") (pintype "bidirectional"))
    )
    (net (code "6") (name "AL1") (class "Default")
      (node (ref "DRIV1") (pin "3") (pinfunction "~{LIN}_3") (pintype "bidirectional"))
      (node (ref "STM1") (pin "PA11") (pinfunction "PA11_PA11") (pintype "bidirectional"))
    )
    (net (code "7") (name "AL2") (class "Default")
      (node (ref "DRIV4") (pin "3") (pinfunction "~{LIN}_3") (pintype "bidirectional"))
      (node (ref "STM1") (pin "PB4") (pinfunction "PB4_PB4") (pintype "bidirectional"))
    )
    (net (code "8") (name "AL3") (class "Default")
      (node (ref "DRIV7") (pin "3") (pinfunction "~{LIN}_3") (pintype "bidirectional"))
      (node (ref "STM2") (pin "PA11") (pinfunction "PA11_PA11") (pintype "bidirectional"))
    )
    (net (code "9") (name "AL4") (class "Default")
      (node (ref "DRIV10") (pin "3") (pinfunction "~{LIN}_3") (pintype "bidirectional"))
      (node (ref "STM2") (pin "PB4") (pinfunction "PB4_PB4") (pintype "bidirectional"))
    )
    (net (code "10") (name "BEMF_A1") (class "Default")
      (node (ref "R37") (pin "2") (pinfunction "2_2") (pintype "passive"))
      (node (ref "STM1") (pin "PA2") (pinfunction "PA2_PA2") (pintype "bidirectional"))
    )
    (net (code "11") (name "BEMF_A2") (class "Default")
      (node (ref "R61") (pin "2") (pinfunction "2_2") (pintype "passive"))
      (node (ref "STM1") (pin "PA5") (pinfunction "PA5_PA5") (pintype "bidirectional"))
    )
    (net (code "12") (name "BEMF_A3") (class "Default")
      (node (ref "R49") (pin "2") (pinfunction "2_2") (pintype "passive"))
      (node (ref "STM2") (pin "PA2") (pinfunction "PA2_PA2") (pintype "bidirectional"))
    )
    (net (code "13") (name "BEMF_A4") (class "Default")
      (node (ref "R73") (pin "2") (pinfunction "2_2") (pintype "passive"))
      (node (ref "STM2") (pin "PA5") (pinfunction "PA5_PA5") (pintype "bidirectional"))
    )
    (net (code "14") (name "BEMF_B1") (class "Default")
      (node (ref "R38") (pin "2") (pinfunction "2_2") (pintype "passive"))
      (node (ref "STM1") (pin "PA3") (pinfunction "PA3_PA3") (pintype "bidirectional"))
    )
    (net (code "15") (name "BEMF_B2") (class "Default")
      (node (ref "R62") (pin "2") (pinfunction "2_2") (pintype "passive"))
      (node (ref "STM1") (pin "PA6") (pinfunction "PA6_PA6") (pintype "bidirectional"))
    )
    (net (code "16") (name "BEMF_B3") (class "Default")
      (node (ref "R50") (pin "2") (pinfunction "2_2") (pintype "passive"))
      (node (ref "STM2") (pin "PA3") (pinfunction "PA3_PA3") (pintype "bidirectional"))
    )
    (net (code "17") (name "BEMF_B4") (class "Default")
      (node (ref "R74") (pin "2") (pinfunction "2_2") (pintype "passive"))
      (node (ref "STM2") (pin "PA6") (pinfunction "PA6_PA6") (pintype "bidirectional"))
    )
    (net (code "18") (name "BEMF_C1") (class "Default")
      (node (ref "R39") (pin "2") (pinfunction "2_2") (pintype "passive"))
      (node (ref "STM1") (pin "PA4") (pinfunction "PA4_PA4") (pintype "bidirectional"))
    )
    (net (code "19") (name "BEMF_C2") (class "Default")
      (node (ref "R63") (pin "2") (pinfunction "2_2") (pintype "passive"))
      (node (ref "STM1") (pin "PA7") (pinfunction "PA7_PA7") (pintype "bidirectional"))
    )
    (net (code "20") (name "BEMF_C3") (class "Default")
      (node (ref "R51") (pin "2") (pinfunction "2_2") (pintype "passive"))
      (node (ref "STM2") (pin "PA4") (pinfunction "PA4_PA4") (pintype "bidirectional"))
    )
    (net (code "21") (name "BEMF_C4") (class "Default")
      (node (ref "R75") (pin "2") (pinfunction "2_2") (pintype "passive"))
      (node (ref "STM2") (pin "PA7") (pinfunction "PA7_PA7") (pintype "bidirectional"))
    )
    (net (code "22") (name "BH1") (class "Default")
      (node (ref "DRIV2") (pin "2") (pinfunction "HIN_2") (pintype "bidirectional"))
      (node (ref "STM1") (pin "PA9") (pinfunction "PA9_PA9") (pintype "bidirectional"))
    )
    (net (code "23") (name "BH2") (class "Default")
      (node (ref "DRIV5") (pin "2") (pinfunction "HIN_2") (pintype "bidirectional"))
      (node (ref "STM1") (pin "PA15") (pinfunction "PA15_PA15") (pintype "bidirectional"))
    )
    (net (code "24") (name "BH3") (class "Default")
      (node (ref "DRIV8") (pin "2") (pinfunction "HIN_2") (pintype "bidirectional"))
      (node (ref "STM2") (pin "PA9") (pinfunction "PA9_PA9") (pintype "bidirectional"))
    )
    (net (code "25") (name "BH4") (class "Default")
      (node (ref "DRIV11") (pin "2") (pinfunction "HIN_2") (pintype "bidirectional"))
      (node (ref "STM2") (pin "PA15") (pinfunction "PA15_PA15") (pintype "bidirectional"))
    )
    (net (code "26") (name "BL1") (class "Default")
      (node (ref "DRIV2") (pin "3") (pinfunction "~{LIN}_3") (pintype "bidirectional"))
      (node (ref "STM1") (pin "PA12") (pinfunction "PA12_PA12") (pintype "bidirectional"))
    )
    (net (code "27") (name "BL2") (class "Default")
      (node (ref "DRIV5") (pin "3") (pinfunction "~{LIN}_3") (pintype "bidirectional"))
      (node (ref "STM1") (pin "PB5") (pinfunction "PB5_PB5") (pintype "bidirectional"))
    )
    (net (code "28") (name "BL3") (class "Default")
      (node (ref "DRIV8") (pin "3") (pinfunction "~{LIN}_3") (pintype "bidirectional"))
      (node (ref "STM2") (pin "PA12") (pinfunction "PA12_PA12") (pintype "bidirectional"))
    )
    (net (code "29") (name "BL4") (class "Default")
      (node (ref "DRIV11") (pin "3") (pinfunction "~{LIN}_3") (pintype "bidirectional"))
      (node (ref "STM2") (pin "PB5") (pinfunction "PB5_PB5") (pintype "bidirectional"))
    )
    (net (code "30") (name "CH1") (class "Default")
      (node (ref "DRIV3") (pin "2") (pinfunction "HIN_2") (pintype "bidirectional"))
      (node (ref "STM1") (pin "PA10") (pinfunction "PA10_PA10") (pintype "bidirectional"))
    )
    (net (code "31") (name "CH2") (class "Default")
      (node (ref "DRIV6") (pin "2") (pinfunction "HIN_2") (pintype "bidirectional"))
      (node (ref "STM1") (pin "PB3") (pinfunction "PB3_PB3") (pintype "bidirectional"))
    )
    (net (code "32") (name "CH3") (class "Default")
      (node (ref "DRIV9") (pin "2") (pinfunction "HIN_2") (pintype "bidirectional"))
      (node (ref "STM2") (pin "PA10") (pinfunction "PA10_PA10") (pintype "bidirectional"))
    )
    (net (code "33") (name "CH4") (class "Default")
      (node (ref "DRIV12") (pin "2") (pinfunction "HIN_2") (pintype "bidirectional"))
      (node (ref "STM2") (pin "PB3") (pinfunction "PB3_PB3") (pintype "bidirectional"))
    )
    (net (code "34") (name "CL1") (class "Default")
      (node (ref "DRIV3") (pin "3") (pinfunction "~{LIN}_3") (pintype "bidirectional"))
      (node (ref "STM1") (pin "PA13") (pinfunction "PA13_PA13") (pintype "bidirectional"))
    )
    (net (code "35") (name "CL2") (class "Default")
      (node (ref "DRIV6") (pin "3") (pinfunction "~{LIN}_3") (pintype "bidirectional"))
      (node (ref "STM1") (pin "PB6") (pinfunction "PB6_PB6") (pintype "bidirectional"))
    )
    (net (code "36") (name "CL3") (class "Default")
      (node (ref "DRIV9") (pin "3") (pinfunction "~{LIN}_3") (pintype "bidirectional"))
      (node (ref "STM2") (pin "PA13") (pinfunction "PA13_PA13") (pintype "bidirectional"))
    )
    (net (code "37") (name "CL4") (class "Default")
      (node (ref "DRIV12") (pin "3") (pinfunction "~{LIN}_3") (pintype "bidirectional"))
      (node (ref "STM2") (pin "PB6") (pinfunction "PB6_PB6") (pintype "bidirectional"))
    )
    (net (code "38") (name "COM1") (class "Default")
      (node (ref "R28") (pin "1") (pinfunction "1_1") (pintype "passive"))
      (node (ref "R29") (pin "1") (pinfunction "1_1") (pintype "passive"))
      (node (ref "R30") (pin "1") (pinfunction "1_1") (pintype "passive"))
      (node (ref "STM1") (pin "PA0") (pinfunction "PA0_PA0") (pintype "bidirectional"))
    )
    (net (code "39") (name "COM2") (class "Default")
      (node (ref "R52") (pin "1") (pinfunction "1_1") (pintype "passive"))
      (node (ref "R53") (pin "1") (pinfunction "1_1") (pintype "passive"))
      (node (ref "R54") (pin "1") (pinfunction "1_1") (pintype "passive"))
      (node (ref "STM1") (pin "PA1") (pinfunction "PA1_PA1") (pintype "bidirectional"))
    )
    (net (code "40") (name "COM3") (class "Default")
      (node (ref "R40") (pin "1") (pinfunction "1_1") (pintype "passive"))
      (node (ref "R41") (pin "1") (pinfunction "1_1") (pintype "passive"))
      (node (ref "R42") (pin "1") (pinfunction "1_1") (pintype "passive"))
      (node (ref "STM2") (pin "PA0") (pinfunction "PA0_PA0") (pintype "bidirectional"))
    )
    (net (code "41") (name "COM4") (class "Default")
      (node (ref "R64") (pin "1") (pinfunction "1_1") (pintype "passive"))
      (node (ref "R65") (pin "1") (pinfunction "1_1") (pintype "passive"))
      (node (ref "R66") (pin "1") (pinfunction "1_1") (pintype "passive"))
      (node (ref "STM2") (pin "PA1") (pinfunction "PA1_PA1") (pintype "bidirectional"))
    )
    (net (code "42") (name "GND") (class "Default")
      (node (ref "C1") (pin "2") (pinfunction "2_2") (pintype "passive"))
      (node (ref "C11") (pin "2") (pinfunction "2_2") (pintype "passive"))
      (node (ref "C13") (pin "2") (pinfunction "2_2") (pintype "passive"))
      (node (ref "C15") (pin "2") (pinfunction "2_2") (pintype "passive"))
      (node (ref "C17") (pin "2") (pinfunction "2_2") (pintype "passive"))
      (node (ref "C19") (pin "2") (pinfunction "2_2") (pintype "passive"))
      (node (ref "C21") (pin "2") (pinfunction "2_2") (pintype "passive"))
      (node (ref "C23") (pin "2") (pinfunction "2_2") (pintype "passive"))
      (node (ref "C25") (pin "2") (pinfunction "2_2") (pintype "passive"))
      (node (ref "C26") (pin "2") (pinfunction "2_2") (pintype "passive"))
      (node (ref "C3") (pin "2") (pinfunction "2_2") (pintype "passive"))
      (node (ref "C5") (pin "2") (pinfunction "2_2") (pintype "passive"))
      (node (ref "C7") (pin "2") (pinfunction "2_2") (pintype "passive"))
      (node (ref "C9") (pin "2") (pinfunction "2_2") (pintype "passive"))
      (node (ref "D1") (pin "C") (pinfunction "C_C") (pintype "passive"))
      (node (ref "D2") (pin "C") (pinfunction "C_C") (pintype "passive"))
      (node (ref "DRIV1") (pin "4") (pinfunction "COM_4") (pintype "bidirectional"))
      (node (ref "DRIV10") (pin "4") (pinfunction "COM_4") (pintype "bidirectional"))
      (node (ref "DRIV11") (pin "4") (pinfunction "COM_4") (pintype "bidirectional"))
      (node (ref "DRIV12") (pin "4") (pinfunction "COM_4") (pintype "bidirectional"))
      (node (ref "DRIV2") (pin "4") (pinfunction "COM_4") (pintype "bidirectional"))
      (node (ref "DRIV3") (pin "4") (pinfunction "COM_4") (pintype "bidirectional"))
      (node (ref "DRIV4") (pin "4") (pinfunction "COM_4") (pintype "bidirectional"))
      (node (ref "DRIV5") (pin "4") (pinfunction "COM_4") (pintype "bidirectional"))
      (node (ref "DRIV6") (pin "4") (pinfunction "COM_4") (pintype "bidirectional"))
      (node (ref "DRIV7") (pin "4") (pinfunction "COM_4") (pintype "bidirectional"))
      (node (ref "DRIV8") (pin "4") (pinfunction "COM_4") (pintype "bidirectional"))
      (node (ref "DRIV9") (pin "4") (pinfunction "COM_4") (pintype "bidirectional"))
      (node (ref "GND_TEST") (pin "1") (pinfunction "1_1") (pintype "passive"))
      (node (ref "MOS10") (pin "2") (pinfunction "DRAIN_2") (pintype "bidirectional"))
      (node (ref "MOS10") (pin "4") (pinfunction "DRAIN_4") (pintype "bidirectional"))
      (node (ref "MOS12") (pin "2") (pinfunction "DRAIN_2") (pintype "bidirectional"))
      (node (ref "MOS12") (pin "4") (pinfunction "DRAIN_4") (pintype "bidirectional"))
      (node (ref "MOS14") (pin "2") (pinfunction "DRAIN_2") (pintype "bidirectional"))
      (node (ref "MOS14") (pin "4") (pinfunction "DRAIN_4") (pintype "bidirectional"))
      (node (ref "MOS16") (pin "2") (pinfunction "DRAIN_2") (pintype "bidirectional"))
      (node (ref "MOS16") (pin "4") (pinfunction "DRAIN_4") (pintype "bidirectional"))
      (node (ref "MOS18") (pin "2") (pinfunction "DRAIN_2") (pintype "bidirectional"))
      (node (ref "MOS18") (pin "4") (pinfunction "DRAIN_4") (pintype "bidirectional"))
      (node (ref "MOS2") (pin "2") (pinfunction "DRAIN_2") (pintype "bidirectional"))
      (node (ref "MOS2") (pin "4") (pinfunction "DRAIN_4") (pintype "bidirectional"))
      (node (ref "MOS20") (pin "2") (pinfunction "DRAIN_2") (pintype "bidirectional"))
      (node (ref "MOS20") (pin "4") (pinfunction "DRAIN_4") (pintype "bidirectional"))
      (node (ref "MOS22") (pin "2") (pinfunction "DRAIN_2") (pintype "bidirectional"))
      (node (ref "MOS22") (pin "4") (pinfunction "DRAIN_4") (pintype "bidirectional"))
      (node (ref "MOS24") (pin "2") (pinfunction "DRAIN_2") (pintype "bidirectional"))
      (node (ref "MOS24") (pin "4") (pinfunction "DRAIN_4") (pintype "bidirectional"))
      (node (ref "MOS4") (pin "2") (pinfunction "DRAIN_2") (pintype "bidirectional"))
      (node (ref "MOS4") (pin "4") (pinfunction "DRAIN_4") (pintype "bidirectional"))
      (node (ref "MOS6") (pin "2") (pinfunction "DRAIN_2") (pintype "bidirectional"))
      (node (ref "MOS6") (pin "4") (pinfunction "DRAIN_4") (pintype "bidirectional"))
      (node (ref "MOS8") (pin "2") (pinfunction "DRAIN_2") (pintype "bidirectional"))
      (node (ref "MOS8") (pin "4") (pinfunction "DRAIN_4") (pintype "bidirectional"))
      (node (ref "POWER") (pin "GND") (pinfunction "GND_GND") (pintype "bidirectional"))
      (node (ref "POWER") (pin "GND@1") (pinfunction "GND_GND@1") (pintype "bidirectional"))
      (node (ref "POWER") (pin "GND@10") (pinfunction "GND_GND@10") (pintype "bidirectional"))
      (node (ref "POWER") (pin "GND@11") (pinfunction "GND_GND@11") (pintype "bidirectional"))
      (node (ref "POWER") (pin "GND@12") (pinfunction "GND_GND@12") (pintype "bidirectional"))
      (node (ref "POWER") (pin "GND@2") (pinfunction "GND_GND@2") (pintype "bidirectional"))
      (node (ref "POWER") (pin "GND@3") (pinfunction "GND_GND@3") (pintype "bidirectional"))
      (node (ref "POWER") (pin "GND@4") (pinfunction "GND_GND@4") (pintype "bidirectional"))
      (node (ref "POWER") (pin "GND@5") (pinfunction "GND_GND@5") (pintype "bidirectional"))
      (node (ref "POWER") (pin "GND@6") (pinfunction "GND_GND@6") (pintype "bidirectional"))
      (node (ref "POWER") (pin "GND@7") (pinfunction "GND_GND@7") (pintype "bidirectional"))
      (node (ref "POWER") (pin "GND@8") (pinfunction "GND_GND@8") (pintype "bidirectional"))
      (node (ref "POWER") (pin "GND@9") (pinfunction "GND_GND@9") (pintype "bidirectional"))
      (node (ref "R34") (pin "1") (pinfunction "1_1") (pintype "passive"))
      (node (ref "R35") (pin "1") (pinfunction "1_1") (pintype "passive"))
      (node (ref "R36") (pin "1") (pinfunction "1_1") (pintype "passive"))
      (node (ref "R46") (pin "1") (pinfunction "1_1") (pintype "passive"))
      (node (ref "R47") (pin "1") (pinfunction "1_1") (pintype "passive"))
      (node (ref "R48") (pin "1") (pinfunction "1_1") (pintype "passive"))
      (node (ref "R58") (pin "1") (pinfunction "1_1") (pintype "passive"))
      (node (ref "R59") (pin "1") (pinfunction "1_1") (pintype "passive"))
      (node (ref "R60") (pin "1") (pinfunction "1_1") (pintype "passive"))
      (node (ref "R70") (pin "1") (pinfunction "1_1") (pintype "passive"))
      (node (ref "R71") (pin "1") (pinfunction "1_1") (pintype "passive"))
      (node (ref "R72") (pin "1") (pinfunction "1_1") (pintype "passive"))
      (node (ref "S1") (pin "1") (pinfunction "1_1") (pintype "passive"))
      (node (ref "STM1") (pin "PB8-BOOT0") (pinfunction "PB8_PB8-BOOT0") (pintype "bidirectional"))
      (node (ref "STM1") (pin "VDDIO2") (pinfunction "VDDIO2_VDDIO2") (pintype "bidirectional"))
      (node (ref "STM1") (pin "VSS") (pinfunction "VSS_VSS") (pintype "bidirectional"))
      (node (ref "STM1") (pin "VSS1") (pinfunction "VSS_VSS1") (pintype "bidirectional"))
      (node (ref "STM2") (pin "PB8-BOOT0") (pinfunction "PB8_PB8-BOOT0") (pintype "bidirectional"))
      (node (ref "STM2") (pin "VDDIO2") (pinfunction "VDDIO2_VDDIO2") (pintype "bidirectional"))
      (node (ref "STM2") (pin "VSS") (pinfunction "VSS_VSS") (pintype "bidirectional"))
      (node (ref "STM2") (pin "VSS1") (pinfunction "VSS_VSS1") (pintype "bidirectional"))
    )
    (net (code "43") (name "LIPO_GND") (class "Default")
      (node (ref "CNTRL") (pin "2") (pinfunction "LIPO_GND_2") (pintype "bidirectional"))
    )
    (net (code "44") (name "LIPO_IN") (class "Default")
      (node (ref "CNTRL") (pin "1") (pinfunction "LIPO_IN_1") (pintype "bidirectional"))
    )
    (net (code "45") (name "NRST") (class "Default")
      (node (ref "C25") (pin "1") (pinfunction "1_1") (pintype "passive"))
      (node (ref "R27") (pin "1") (pinfunction "1_1") (pintype "passive"))
      (node (ref "S1") (pin "2") (pinfunction "2_2") (pintype "passive"))
      (node (ref "STM1") (pin "NRST") (pinfunction "NRST_NRST") (pintype "bidirectional"))
      (node (ref "STM2") (pin "NRST") (pinfunction "NRST_NRST") (pintype "bidirectional"))
    )
    (net (code "46") (name "Net-(D1-PadA)") (class "Default")
      (node (ref "D1") (pin "A") (pinfunction "A_A") (pintype "passive"))
      (node (ref "R1") (pin "1") (pinfunction "1_1") (pintype "passive"))
    )
    (net (code "47") (name "Net-(D2-PadA)") (class "Default")
      (node (ref "D2") (pin "A") (pinfunction "A_A") (pintype "passive"))
      (node (ref "R2") (pin "1") (pinfunction "1_1") (pintype "passive"))
    )
    (net (code "48") (name "Net-(DRIV1-HO)") (class "Default")
      (node (ref "DRIV1") (pin "7") (pinfunction "HO_7") (pintype "bidirectional"))
      (node (ref "R3") (pin "1") (pinfunction "1_1") (pintype "passive"))
    )
    (net (code "49") (name "Net-(DRIV1-LO)") (class "Default")
      (node (ref "DRIV1") (pin "5") (pinfunction "LO_5") (pintype "bidirectional"))
      (node (ref "R4") (pin "1") (pinfunction "1_1") (pintype "passive"))
    )
    (net (code "50") (name "Net-(DRIV1-VB)") (class "Default")
      (node (ref "C2") (pin "1") (pinfunction "1_1") (pintype "passive"))
      (node (ref "D3") (pin "P$2") (pinfunction "P$2_P$2") (pintype "bidirectional"))
      (node (ref "DRIV1") (pin "8") (pinfunction "VB_8") (pintype "bidirectional"))
    )
    (net (code "51") (name "Net-(DRIV2-HO)") (class "Default")
      (node (ref "DRIV2") (pin "7") (pinfunction "HO_7") (pintype "bidirectional"))
      (node (ref "R5") (pin "1") (pinfunction "1_1") (pintype "passive"))
    )
    (net (code "52") (name "Net-(DRIV2-LO)") (class "Default")
      (node (ref "DRIV2") (pin "5") (pinfunction "LO_5") (pintype "bidirectional"))
      (node (ref "R6") (pin "1") (pinfunction "1_1") (pintype "passive"))
    )
    (net (code "53") (name "Net-(DRIV2-VB)") (class "Default")
      (node (ref "C4") (pin "1") (pinfunction "1_1") (pintype "passive"))
      (node (ref "D4") (pin "P$2") (pinfunction "P$2_P$2") (pintype "bidirectional"))
      (node (ref "DRIV2") (pin "8") (pinfunction "VB_8") (pintype "bidirectional"))
    )
    (net (code "54") (name "Net-(DRIV3-HO)") (class "Default")
      (node (ref "DRIV3") (pin "7") (pinfunction "HO_7") (pintype "bidirectional"))
      (node (ref "R7") (pin "1") (pinfunction "1_1") (pintype "passive"))
    )
    (net (code "55") (name "Net-(DRIV3-LO)") (class "Default")
      (node (ref "DRIV3") (pin "5") (pinfunction "LO_5") (pintype "bidirectional"))
      (node (ref "R8") (pin "1") (pinfunction "1_1") (pintype "passive"))
    )
    (net (code "56") (name "Net-(DRIV3-VB)") (class "Default")
      (node (ref "C6") (pin "1") (pinfunction "1_1") (pintype "passive"))
      (node (ref "D5") (pin "P$2") (pinfunction "P$2_P$2") (pintype "bidirectional"))
      (node (ref "DRIV3") (pin "8") (pinfunction "VB_8") (pintype "bidirectional"))
    )
    (net (code "57") (name "Net-(DRIV4-HO)") (class "Default")
      (node (ref "DRIV4") (pin "7") (pinfunction "HO_7") (pintype "bidirectional"))
      (node (ref "R9") (pin "1") (pinfunction "1_1") (pintype "passive"))
    )
    (net (code "58") (name "Net-(DRIV4-LO)") (class "Default")
      (node (ref "DRIV4") (pin "5") (pinfunction "LO_5") (pintype "bidirectional"))
      (node (ref "R10") (pin "1") (pinfunction "1_1") (pintype "passive"))
    )
    (net (code "59") (name "Net-(DRIV4-VB)") (class "Default")
      (node (ref "C8") (pin "1") (pinfunction "1_1") (pintype "passive"))
      (node (ref "D6") (pin "P$2") (pinfunction "P$2_P$2") (pintype "bidirectional"))
      (node (ref "DRIV4") (pin "8") (pinfunction "VB_8") (pintype "bidirectional"))
    )
    (net (code "60") (name "Net-(DRIV5-HO)") (class "Default")
      (node (ref "DRIV5") (pin "7") (pinfunction "HO_7") (pintype "bidirectional"))
      (node (ref "R11") (pin "1") (pinfunction "1_1") (pintype "passive"))
    )
    (net (code "61") (name "Net-(DRIV5-LO)") (class "Default")
      (node (ref "DRIV5") (pin "5") (pinfunction "LO_5") (pintype "bidirectional"))
      (node (ref "R12") (pin "1") (pinfunction "1_1") (pintype "passive"))
    )
    (net (code "62") (name "Net-(DRIV5-VB)") (class "Default")
      (node (ref "C10") (pin "1") (pinfunction "1_1") (pintype "passive"))
      (node (ref "D7") (pin "P$2") (pinfunction "P$2_P$2") (pintype "bidirectional"))
      (node (ref "DRIV5") (pin "8") (pinfunction "VB_8") (pintype "bidirectional"))
    )
    (net (code "63") (name "Net-(DRIV6-HO)") (class "Default")
      (node (ref "DRIV6") (pin "7") (pinfunction "HO_7") (pintype "bidirectional"))
      (node (ref "R13") (pin "1") (pinfunction "1_1") (pintype "passive"))
    )
    (net (code "64") (name "Net-(DRIV6-LO)") (class "Default")
      (node (ref "DRIV6") (pin "5") (pinfunction "LO_5") (pintype "bidirectional"))
      (node (ref "R14") (pin "1") (pinfunction "1_1") (pintype "passive"))
    )
    (net (code "65") (name "Net-(DRIV6-VB)") (class "Default")
      (node (ref "C12") (pin "1") (pinfunction "1_1") (pintype "passive"))
      (node (ref "D8") (pin "P$2") (pinfunction "P$2_P$2") (pintype "bidirectional"))
      (node (ref "DRIV6") (pin "8") (pinfunction "VB_8") (pintype "bidirectional"))
    )
    (net (code "66") (name "Net-(DRIV7-HO)") (class "Default")
      (node (ref "DRIV7") (pin "7") (pinfunction "HO_7") (pintype "bidirectional"))
      (node (ref "R15") (pin "1") (pinfunction "1_1") (pintype "passive"))
    )
    (net (code "67") (name "Net-(DRIV7-LO)") (class "Default")
      (node (ref "DRIV7") (pin "5") (pinfunction "LO_5") (pintype "bidirectional"))
      (node (ref "R16") (pin "1") (pinfunction "1_1") (pintype "passive"))
    )
    (net (code "68") (name "Net-(DRIV7-VB)") (class "Default")
      (node (ref "C14") (pin "1") (pinfunction "1_1") (pintype "passive"))
      (node (ref "D9") (pin "P$2") (pinfunction "P$2_P$2") (pintype "bidirectional"))
      (node (ref "DRIV7") (pin "8") (pinfunction "VB_8") (pintype "bidirectional"))
    )
    (net (code "69") (name "Net-(DRIV8-HO)") (class "Default")
      (node (ref "DRIV8") (pin "7") (pinfunction "HO_7") (pintype "bidirectional"))
      (node (ref "R17") (pin "1") (pinfunction "1_1") (pintype "passive"))
    )
    (net (code "70") (name "Net-(DRIV8-LO)") (class "Default")
      (node (ref "DRIV8") (pin "5") (pinfunction "LO_5") (pintype "bidirectional"))
      (node (ref "R18") (pin "1") (pinfunction "1_1") (pintype "passive"))
    )
    (net (code "71") (name "Net-(DRIV8-VB)") (class "Default")
      (node (ref "C16") (pin "1") (pinfunction "1_1") (pintype "passive"))
      (node (ref "D10") (pin "P$2") (pinfunction "P$2_P$2") (pintype "bidirectional"))
      (node (ref "DRIV8") (pin "8") (pinfunction "VB_8") (pintype "bidirectional"))
    )
    (net (code "72") (name "Net-(DRIV9-HO)") (class "Default")
      (node (ref "DRIV9") (pin "7") (pinfunction "HO_7") (pintype "bidirectional"))
      (node (ref "R19") (pin "1") (pinfunction "1_1") (pintype "passive"))
    )
    (net (code "73") (name "Net-(DRIV9-LO)") (class "Default")
      (node (ref "DRIV9") (pin "5") (pinfunction "LO_5") (pintype "bidirectional"))
      (node (ref "R20") (pin "1") (pinfunction "1_1") (pintype "passive"))
    )
    (net (code "74") (name "Net-(DRIV9-VB)") (class "Default")
      (node (ref "C18") (pin "1") (pinfunction "1_1") (pintype "passive"))
      (node (ref "D11") (pin "P$2") (pinfunction "P$2_P$2") (pintype "bidirectional"))
      (node (ref "DRIV9") (pin "8") (pinfunction "VB_8") (pintype "bidirectional"))
    )
    (net (code "75") (name "Net-(DRIV10-HO)") (class "Default")
      (node (ref "DRIV10") (pin "7") (pinfunction "HO_7") (pintype "bidirectional"))
      (node (ref "R21") (pin "1") (pinfunction "1_1") (pintype "passive"))
    )
    (net (code "76") (name "Net-(DRIV10-LO)") (class "Default")
      (node (ref "DRIV10") (pin "5") (pinfunction "LO_5") (pintype "bidirectional"))
      (node (ref "R22") (pin "1") (pinfunction "1_1") (pintype "passive"))
    )
    (net (code "77") (name "Net-(DRIV10-VB)") (class "Default")
      (node (ref "C20") (pin "1") (pinfunction "1_1") (pintype "passive"))
      (node (ref "D12") (pin "P$2") (pinfunction "P$2_P$2") (pintype "bidirectional"))
      (node (ref "DRIV10") (pin "8") (pinfunction "VB_8") (pintype "bidirectional"))
    )
    (net (code "78") (name "Net-(DRIV11-HO)") (class "Default")
      (node (ref "DRIV11") (pin "7") (pinfunction "HO_7") (pintype "bidirectional"))
      (node (ref "R23") (pin "1") (pinfunction "1_1") (pintype "passive"))
    )
    (net (code "79") (name "Net-(DRIV11-LO)") (class "Default")
      (node (ref "DRIV11") (pin "5") (pinfunction "LO_5") (pintype "bidirectional"))
      (node (ref "R24") (pin "1") (pinfunction "1_1") (pintype "passive"))
    )
    (net (code "80") (name "Net-(DRIV11-VB)") (class "Default")
      (node (ref "C22") (pin "1") (pinfunction "1_1") (pintype "passive"))
      (node (ref "D13") (pin "P$2") (pinfunction "P$2_P$2") (pintype "bidirectional"))
      (node (ref "DRIV11") (pin "8") (pinfunction "VB_8") (pintype "bidirectional"))
    )
    (net (code "81") (name "Net-(DRIV12-HO)") (class "Default")
      (node (ref "DRIV12") (pin "7") (pinfunction "HO_7") (pintype "bidirectional"))
      (node (ref "R25") (pin "1") (pinfunction "1_1") (pintype "passive"))
    )
    (net (code "82") (name "Net-(DRIV12-LO)") (class "Default")
      (node (ref "DRIV12") (pin "5") (pinfunction "LO_5") (pintype "bidirectional"))
      (node (ref "R26") (pin "1") (pinfunction "1_1") (pintype "passive"))
    )
    (net (code "83") (name "Net-(DRIV12-VB)") (class "Default")
      (node (ref "C24") (pin "1") (pinfunction "1_1") (pintype "passive"))
      (node (ref "D14") (pin "P$2") (pinfunction "P$2_P$2") (pintype "bidirectional"))
      (node (ref "DRIV12") (pin "8") (pinfunction "VB_8") (pintype "bidirectional"))
    )
    (net (code "84") (name "Net-(MOS1-GATE)") (class "Default")
      (node (ref "MOS1") (pin "1") (pinfunction "GATE_1") (pintype "bidirectional"))
      (node (ref "R3") (pin "2") (pinfunction "2_2") (pintype "passive"))
    )
    (net (code "85") (name "Net-(MOS2-GATE)") (class "Default")
      (node (ref "MOS2") (pin "1") (pinfunction "GATE_1") (pintype "bidirectional"))
      (node (ref "R4") (pin "2") (pinfunction "2_2") (pintype "passive"))
    )
    (net (code "86") (name "Net-(MOS3-GATE)") (class "Default")
      (node (ref "MOS3") (pin "1") (pinfunction "GATE_1") (pintype "bidirectional"))
      (node (ref "R5") (pin "2") (pinfunction "2_2") (pintype "passive"))
    )
    (net (code "87") (name "Net-(MOS4-GATE)") (class "Default")
      (node (ref "MOS4") (pin "1") (pinfunction "GATE_1") (pintype "bidirectional"))
      (node (ref "R6") (pin "2") (pinfunction "2_2") (pintype "passive"))
    )
    (net (code "88") (name "Net-(MOS5-GATE)") (class "Default")
      (node (ref "MOS5") (pin "1") (pinfunction "GATE_1") (pintype "bidirectional"))
      (node (ref "R7") (pin "2") (pinfunction "2_2") (pintype "passive"))
    )
    (net (code "89") (name "Net-(MOS6-GATE)") (class "Default")
      (node (ref "MOS6") (pin "1") (pinfunction "GATE_1") (pintype "bidirectional"))
      (node (ref "R8") (pin "2") (pinfunction "2_2") (pintype "passive"))
    )
    (net (code "90") (name "Net-(MOS7-GATE)") (class "Default")
      (node (ref "MOS7") (pin "1") (pinfunction "GATE_1") (pintype "bidirectional"))
      (node (ref "R9") (pin "2") (pinfunction "2_2") (pintype "passive"))
    )
    (net (code "91") (name "Net-(MOS8-GATE)") (class "Default")
      (node (ref "MOS8") (pin "1") (pinfunction "GATE_1") (pintype "bidirectional"))
      (node (ref "R10") (pin "2") (pinfunction "2_2") (pintype "passive"))
    )
    (net (code "92") (name "Net-(MOS9-GATE)") (class "Default")
      (node (ref "MOS9") (pin "1") (pinfunction "GATE_1") (pintype "bidirectional"))
      (node (ref "R11") (pin "2") (pinfunction "2_2") (pintype "passive"))
    )
    (net (code "93") (name "Net-(MOS10-GATE)") (class "Default")
      (node (ref "MOS10") (pin "1") (pinfunction "GATE_1") (pintype "bidirectional"))
      (node (ref "R12") (pin "2") (pinfunction "2_2") (pintype "passive"))
    )
    (net (code "94") (name "Net-(MOS11-GATE)") (class "Default")
      (node (ref "MOS11") (pin "1") (pinfunction "GATE_1") (pintype "bidirectional"))
      (node (ref "R13") (pin "2") (pinfunction "2_2") (pintype "passive"))
    )
    (net (code "95") (name "Net-(MOS12-GATE)") (class "Default")
      (node (ref "MOS12") (pin "1") (pinfunction "GATE_1") (pintype "bidirectional"))
      (node (ref "R14") (pin "2") (pinfunction "2_2") (pintype "passive"))
    )
    (net (code "96") (name "Net-(MOS13-GATE)") (class "Default")
      (node (ref "MOS13") (pin "1") (pinfunction "GATE_1") (pintype "bidirectional"))
      (node (ref "R15") (pin "2") (pinfunction "2_2") (pintype "passive"))
    )
    (net (code "97") (name "Net-(MOS14-GATE)") (class "Default")
      (node (ref "MOS14") (pin "1") (pinfunction "GATE_1") (pintype "bidirectional"))
      (node (ref "R16") (pin "2") (pinfunction "2_2") (pintype "passive"))
    )
    (net (code "98") (name "Net-(MOS15-GATE)") (class "Default")
      (node (ref "MOS15") (pin "1") (pinfunction "GATE_1") (pintype "bidirectional"))
      (node (ref "R17") (pin "2") (pinfunction "2_2") (pintype "passive"))
    )
    (net (code "99") (name "Net-(MOS16-GATE)") (class "Default")
      (node (ref "MOS16") (pin "1") (pinfunction "GATE_1") (pintype "bidirectional"))
      (node (ref "R18") (pin "2") (pinfunction "2_2") (pintype "passive"))
    )
    (net (code "100") (name "Net-(MOS17-GATE)") (class "Default")
      (node (ref "MOS17") (pin "1") (pinfunction "GATE_1") (pintype "bidirectional"))
      (node (ref "R19") (pin "2") (pinfunction "2_2") (pintype "passive"))
    )
    (net (code "101") (name "Net-(MOS18-GATE)") (class "Default")
      (node (ref "MOS18") (pin "1") (pinfunction "GATE_1") (pintype "bidirectional"))
      (node (ref "R20") (pin "2") (pinfunction "2_2") (pintype "passive"))
    )
    (net (code "102") (name "Net-(MOS19-GATE)") (class "Default")
      (node (ref "MOS19") (pin "1") (pinfunction "GATE_1") (pintype "bidirectional"))
      (node (ref "R21") (pin "2") (pinfunction "2_2") (pintype "passive"))
    )
    (net (code "103") (name "Net-(MOS20-GATE)") (class "Default")
      (node (ref "MOS20") (pin "1") (pinfunction "GATE_1") (pintype "bidirectional"))
      (node (ref "R22") (pin "2") (pinfunction "2_2") (pintype "passive"))
    )
    (net (code "104") (name "Net-(MOS21-GATE)") (class "Default")
      (node (ref "MOS21") (pin "1") (pinfunction "GATE_1") (pintype "bidirectional"))
      (node (ref "R23") (pin "2") (pinfunction "2_2") (pintype "passive"))
    )
    (net (code "105") (name "Net-(MOS22-GATE)") (class "Default")
      (node (ref "MOS22") (pin "1") (pinfunction "GATE_1") (pintype "bidirectional"))
      (node (ref "R24") (pin "2") (pinfunction "2_2") (pintype "passive"))
    )
    (net (code "106") (name "Net-(MOS23-GATE)") (class "Default")
      (node (ref "MOS23") (pin "1") (pinfunction "GATE_1") (pintype "bidirectional"))
      (node (ref "R25") (pin "2") (pinfunction "2_2") (pintype "passive"))
    )
    (net (code "107") (name "Net-(MOS24-GATE)") (class "Default")
      (node (ref "MOS24") (pin "1") (pinfunction "GATE_1") (pintype "bidirectional"))
      (node (ref "R26") (pin "2") (pinfunction "2_2") (pintype "passive"))
    )
    (net (code "108") (name "Net-(R28-Pad2)") (class "Default")
      (node (ref "R28") (pin "2") (pinfunction "2_2") (pintype "passive"))
      (node (ref "R31") (pin "1") (pinfunction "1_1") (pintype "passive"))
      (node (ref "R34") (pin "2") (pinfunction "2_2") (pintype "passive"))
      (node (ref "R37") (pin "1") (pinfunction "1_1") (pintype "passive"))
    )
    (net (code "109") (name "Net-(R29-Pad2)") (class "Default")
      (node (ref "R29") (pin "2") (pinfunction "2_2") (pintype "passive"))
      (node (ref "R32") (pin "1") (pinfunction "1_1") (pintype "passive"))
      (node (ref "R35") (pin "2") (pinfunction "2_2") (pintype "passive"))
      (node (ref "R38") (pin "1") (pinfunction "1_1") (pintype "passive"))
    )
    (net (code "110") (name "Net-(R30-Pad2)") (class "Default")
      (node (ref "R30") (pin "2") (pinfunction "2_2") (pintype "passive"))
      (node (ref "R33") (pin "1") (pinfunction "1_1") (pintype "passive"))
      (node (ref "R36") (pin "2") (pinfunction "2_2") (pintype "passive"))
      (node (ref "R39") (pin "1") (pinfunction "1_1") (pintype "passive"))
    )
    (net (code "111") (name "Net-(R40-Pad2)") (class "Default")
      (node (ref "R40") (pin "2") (pinfunction "2_2") (pintype "passive"))
      (node (ref "R43") (pin "1") (pinfunction "1_1") (pintype "passive"))
      (node (ref "R46") (pin "2") (pinfunction "2_2") (pintype "passive"))
      (node (ref "R49") (pin "1") (pinfunction "1_1") (pintype "passive"))
    )
    (net (code "112") (name "Net-(R41-Pad2)") (class "Default")
      (node (ref "R41") (pin "2") (pinfunction "2_2") (pintype "passive"))
      (node (ref "R44") (pin "1") (pinfunction "1_1") (pintype "passive"))
      (node (ref "R47") (pin "2") (pinfunction "2_2") (pintype "passive"))
      (node (ref "R50") (pin "1") (pinfunction "1_1") (pintype "passive"))
    )
    (net (code "113") (name "Net-(R42-Pad2)") (class "Default")
      (node (ref "R42") (pin "2") (pinfunction "2_2") (pintype "passive"))
      (node (ref "R45") (pin "1") (pinfunction "1_1") (pintype "passive"))
      (node (ref "R48") (pin "2") (pinfunction "2_2") (pintype "passive"))
      (node (ref "R51") (pin "1") (pinfunction "1_1") (pintype "passive"))
    )
    (net (code "114") (name "Net-(R52-Pad2)") (class "Default")
      (node (ref "R52") (pin "2") (pinfunction "2_2") (pintype "passive"))
      (node (ref "R55") (pin "1") (pinfunction "1_1") (pintype "passive"))
      (node (ref "R58") (pin "2") (pinfunction "2_2") (pintype "passive"))
      (node (ref "R61") (pin "1") (pinfunction "1_1") (pintype "passive"))
    )
    (net (code "115") (name "Net-(R53-Pad2)") (class "Default")
      (node (ref "R53") (pin "2") (pinfunction "2_2") (pintype "passive"))
      (node (ref "R56") (pin "1") (pinfunction "1_1") (pintype "passive"))
      (node (ref "R59") (pin "2") (pinfunction "2_2") (pintype "passive"))
      (node (ref "R62") (pin "1") (pinfunction "1_1") (pintype "passive"))
    )
    (net (code "116") (name "Net-(R54-Pad2)") (class "Default")
      (node (ref "R54") (pin "2") (pinfunction "2_2") (pintype "passive"))
      (node (ref "R57") (pin "1") (pinfunction "1_1") (pintype "passive"))
      (node (ref "R60") (pin "2") (pinfunction "2_2") (pintype "passive"))
      (node (ref "R63") (pin "1") (pinfunction "1_1") (pintype "passive"))
    )
    (net (code "117") (name "Net-(R64-Pad2)") (class "Default")
      (node (ref "R64") (pin "2") (pinfunction "2_2") (pintype "passive"))
      (node (ref "R67") (pin "1") (pinfunction "1_1") (pintype "passive"))
      (node (ref "R70") (pin "2") (pinfunction "2_2") (pintype "passive"))
      (node (ref "R73") (pin "1") (pinfunction "1_1") (pintype "passive"))
    )
    (net (code "118") (name "Net-(R65-Pad2)") (class "Default")
      (node (ref "R65") (pin "2") (pinfunction "2_2") (pintype "passive"))
      (node (ref "R68") (pin "1") (pinfunction "1_1") (pintype "passive"))
      (node (ref "R71") (pin "2") (pinfunction "2_2") (pintype "passive"))
      (node (ref "R74") (pin "1") (pinfunction "1_1") (pintype "passive"))
    )
    (net (code "119") (name "Net-(R66-Pad2)") (class "Default")
      (node (ref "R66") (pin "2") (pinfunction "2_2") (pintype "passive"))
      (node (ref "R69") (pin "1") (pinfunction "1_1") (pintype "passive"))
      (node (ref "R72") (pin "2") (pinfunction "2_2") (pintype "passive"))
      (node (ref "R75") (pin "1") (pinfunction "1_1") (pintype "passive"))
    )
    (net (code "120") (name "PHASE_A1") (class "Default")
      (node (ref "C2") (pin "2") (pinfunction "2_2") (pintype "passive"))
      (node (ref "DRIV1") (pin "6") (pinfunction "VS_6") (pintype "bidirectional"))
      (node (ref "MOS1") (pin "2") (pinfunction "DRAIN_2") (pintype "bidirectional"))
      (node (ref "MOS1") (pin "4") (pinfunction "DRAIN_4") (pintype "bidirectional"))
      (node (ref "MOS2") (pin "3") (pinfunction "SOURCE_3") (pintype "bidirectional"))
      (node (ref "OUT1") (pin "1") (pinfunction "A_1") (pintype "bidirectional"))
      (node (ref "R31") (pin "2") (pinfunction "2_2") (pintype "passive"))
    )
    (net (code "121") (name "PHASE_A2") (class "Default")
      (node (ref "C8") (pin "2") (pinfunction "2_2") (pintype "passive"))
      (node (ref "DRIV4") (pin "6") (pinfunction "VS_6") (pintype "bidirectional"))
      (node (ref "MOS7") (pin "2") (pinfunction "DRAIN_2") (pintype "bidirectional"))
      (node (ref "MOS7") (pin "4") (pinfunction "DRAIN_4") (pintype "bidirectional"))
      (node (ref "MOS8") (pin "3") (pinfunction "SOURCE_3") (pintype "bidirectional"))
      (node (ref "OUT2") (pin "1") (pinfunction "A_1") (pintype "bidirectional"))
      (node (ref "R55") (pin "2") (pinfunction "2_2") (pintype "passive"))
    )
    (net (code "122") (name "PHASE_A3") (class "Default")
      (node (ref "C14") (pin "2") (pinfunction "2_2") (pintype "passive"))
      (node (ref "DRIV7") (pin "6") (pinfunction "VS_6") (pintype "bidirectional"))
      (node (ref "MOS13") (pin "2") (pinfunction "DRAIN_2") (pintype "bidirectional"))
      (node (ref "MOS13") (pin "4") (pinfunction "DRAIN_4") (pintype "bidirectional"))
      (node (ref "MOS14") (pin "3") (pinfunction "SOURCE_3") (pintype "bidirectional"))
      (node (ref "OUT3") (pin "1") (pinfunction "A_1") (pintype "bidirectional"))
      (node (ref "R43") (pin "2") (pinfunction "2_2") (pintype "passive"))
    )
    (net (code "123") (name "PHASE_A4") (class "Default")
      (node (ref "C20") (pin "2") (pinfunction "2_2") (pintype "passive"))
      (node (ref "DRIV10") (pin "6") (pinfunction "VS_6") (pintype "bidirectional"))
      (node (ref "MOS19") (pin "2") (pinfunction "DRAIN_2") (pintype "bidirectional"))
      (node (ref "MOS19") (pin "4") (pinfunction "DRAIN_4") (pintype "bidirectional"))
      (node (ref "MOS20") (pin "3") (pinfunction "SOURCE_3") (pintype "bidirectional"))
      (node (ref "OUT4") (pin "1") (pinfunction "A_1") (pintype "bidirectional"))
      (node (ref "R67") (pin "2") (pinfunction "2_2") (pintype "passive"))
    )
    (net (code "124") (name "PHASE_B1") (class "Default")
      (node (ref "C4") (pin "2") (pinfunction "2_2") (pintype "passive"))
      (node (ref "DRIV2") (pin "6") (pinfunction "VS_6") (pintype "bidirectional"))
      (node (ref "MOS3") (pin "2") (pinfunction "DRAIN_2") (pintype "bidirectional"))
      (node (ref "MOS3") (pin "4") (pinfunction "DRAIN_4") (pintype "bidirectional"))
      (node (ref "MOS4") (pin "3") (pinfunction "SOURCE_3") (pintype "bidirectional"))
      (node (ref "OUT1") (pin "2") (pinfunction "B_2") (pintype "bidirectional"))
      (node (ref "R32") (pin "2") (pinfunction "2_2") (pintype "passive"))
    )
    (net (code "125") (name "PHASE_B2") (class "Default")
      (node (ref "C10") (pin "2") (pinfunction "2_2") (pintype "passive"))
      (node (ref "DRIV5") (pin "6") (pinfunction "VS_6") (pintype "bidirectional"))
      (node (ref "MOS10") (pin "3") (pinfunction "SOURCE_3") (pintype "bidirectional"))
      (node (ref "MOS9") (pin "2") (pinfunction "DRAIN_2") (pintype "bidirectional"))
      (node (ref "MOS9") (pin "4") (pinfunction "DRAIN_4") (pintype "bidirectional"))
      (node (ref "OUT2") (pin "2") (pinfunction "B_2") (pintype "bidirectional"))
      (node (ref "R56") (pin "2") (pinfunction "2_2") (pintype "passive"))
    )
    (net (code "126") (name "PHASE_B3") (class "Default")
      (node (ref "C16") (pin "2") (pinfunction "2_2") (pintype "passive"))
      (node (ref "DRIV8") (pin "6") (pinfunction "VS_6") (pintype "bidirectional"))
      (node (ref "MOS15") (pin "2") (pinfunction "DRAIN_2") (pintype "bidirectional"))
      (node (ref "MOS15") (pin "4") (pinfunction "DRAIN_4") (pintype "bidirectional"))
      (node (ref "MOS16") (pin "3") (pinfunction "SOURCE_3") (pintype "bidirectional"))
      (node (ref "OUT3") (pin "2") (pinfunction "B_2") (pintype "bidirectional"))
      (node (ref "R44") (pin "2") (pinfunction "2_2") (pintype "passive"))
    )
    (net (code "127") (name "PHASE_B4") (class "Default")
      (node (ref "C22") (pin "2") (pinfunction "2_2") (pintype "passive"))
      (node (ref "DRIV11") (pin "6") (pinfunction "VS_6") (pintype "bidirectional"))
      (node (ref "MOS21") (pin "2") (pinfunction "DRAIN_2") (pintype "bidirectional"))
      (node (ref "MOS21") (pin "4") (pinfunction "DRAIN_4") (pintype "bidirectional"))
      (node (ref "MOS22") (pin "3") (pinfunction "SOURCE_3") (pintype "bidirectional"))
      (node (ref "OUT4") (pin "2") (pinfunction "B_2") (pintype "bidirectional"))
      (node (ref "R68") (pin "2") (pinfunction "2_2") (pintype "passive"))
    )
    (net (code "128") (name "PHASE_C1") (class "Default")
      (node (ref "C6") (pin "2") (pinfunction "2_2") (pintype "passive"))
      (node (ref "DRIV3") (pin "6") (pinfunction "VS_6") (pintype "bidirectional"))
      (node (ref "MOS5") (pin "2") (pinfunction "DRAIN_2") (pintype "bidirectional"))
      (node (ref "MOS5") (pin "4") (pinfunction "DRAIN_4") (pintype "bidirectional"))
      (node (ref "MOS6") (pin "3") (pinfunction "SOURCE_3") (pintype "bidirectional"))
      (node (ref "OUT1") (pin "3") (pinfunction "C_3") (pintype "bidirectional"))
      (node (ref "R33") (pin "2") (pinfunction "2_2") (pintype "passive"))
    )
    (net (code "129") (name "PHASE_C2") (class "Default")
      (node (ref "C12") (pin "2") (pinfunction "2_2") (pintype "passive"))
      (node (ref "DRIV6") (pin "6") (pinfunction "VS_6") (pintype "bidirectional"))
      (node (ref "MOS11") (pin "2") (pinfunction "DRAIN_2") (pintype "bidirectional"))
      (node (ref "MOS11") (pin "4") (pinfunction "DRAIN_4") (pintype "bidirectional"))
      (node (ref "MOS12") (pin "3") (pinfunction "SOURCE_3") (pintype "bidirectional"))
      (node (ref "OUT2") (pin "3") (pinfunction "C_3") (pintype "bidirectional"))
      (node (ref "R57") (pin "2") (pinfunction "2_2") (pintype "passive"))
    )
    (net (code "130") (name "PHASE_C3") (class "Default")
      (node (ref "C18") (pin "2") (pinfunction "2_2") (pintype "passive"))
      (node (ref "DRIV9") (pin "6") (pinfunction "VS_6") (pintype "bidirectional"))
      (node (ref "MOS17") (pin "2") (pinfunction "DRAIN_2") (pintype "bidirectional"))
      (node (ref "MOS17") (pin "4") (pinfunction "DRAIN_4") (pintype "bidirectional"))
      (node (ref "MOS18") (pin "3") (pinfunction "SOURCE_3") (pintype "bidirectional"))
      (node (ref "OUT3") (pin "3") (pinfunction "C_3") (pintype "bidirectional"))
      (node (ref "R45") (pin "2") (pinfunction "2_2") (pintype "passive"))
    )
    (net (code "131") (name "PHASE_C4") (class "Default")
      (node (ref "C24") (pin "2") (pinfunction "2_2") (pintype "passive"))
      (node (ref "DRIV12") (pin "6") (pinfunction "VS_6") (pintype "bidirectional"))
      (node (ref "MOS23") (pin "2") (pinfunction "DRAIN_2") (pintype "bidirectional"))
      (node (ref "MOS23") (pin "4") (pinfunction "DRAIN_4") (pintype "bidirectional"))
      (node (ref "MOS24") (pin "3") (pinfunction "SOURCE_3") (pintype "bidirectional"))
      (node (ref "OUT4") (pin "3") (pinfunction "C_3") (pintype "bidirectional"))
      (node (ref "R69") (pin "2") (pinfunction "2_2") (pintype "passive"))
    )
    (net (code "132") (name "TIM1") (class "Default")
      (node (ref "CNTRL") (pin "5") (pinfunction "MTR_1_5") (pintype "bidirectional"))
      (node (ref "STM1") (pin "PB0") (pinfunction "PB0_PB0") (pintype "bidirectional"))
    )
    (net (code "133") (name "TIM2") (class "Default")
      (node (ref "CNTRL") (pin "6") (pinfunction "MTR_2_6") (pintype "bidirectional"))
      (node (ref "STM1") (pin "PB1") (pinfunction "PB1_PB1") (pintype "bidirectional"))
    )
    (net (code "134") (name "TIM3") (class "Default")
      (node (ref "CNTRL") (pin "7") (pinfunction "MTR_3_7") (pintype "bidirectional"))
      (node (ref "STM2") (pin "PB0") (pinfunction "PB0_PB0") (pintype "bidirectional"))
    )
    (net (code "135") (name "TIM4") (class "Default")
      (node (ref "CNTRL") (pin "8") (pinfunction "MTR_4_8") (pintype "bidirectional"))
      (node (ref "STM2") (pin "PB1") (pinfunction "PB1_PB1") (pintype "bidirectional"))
    )
    (net (code "136") (name "TLM") (class "Default")
      (node (ref "CNTRL") (pin "4") (pinfunction "TLM_4") (pintype "bidirectional"))
    )
    (net (code "137") (name "VCC_1") (class "Default")
      (node (ref "3.3V_TEST") (pin "1") (pinfunction "1_1") (pintype "passive"))
      (node (ref "C26") (pin "1") (pinfunction "1_1") (pintype "passive"))
      (node (ref "POWER") (pin "3.3V") (pinfunction "3.3V_3.3V") (pintype "bidirectional"))
      (node (ref "R1") (pin "2") (pinfunction "2_2") (pintype "passive"))
      (node (ref "R27") (pin "2") (pinfunction "2_2") (pintype "passive"))
      (node (ref "STM1") (pin "VDD") (pinfunction "VDD_VDD") (pintype "bidirectional"))
      (node (ref "STM1") (pin "VDDA") (pinfunction "VDDA_VDDA") (pintype "bidirectional"))
      (node (ref "STM2") (pin "VDD") (pinfunction "VDD_VDD") (pintype "bidirectional"))
      (node (ref "STM2") (pin "VDDA") (pinfunction "VDDA_VDDA") (pintype "bidirectional"))
    )
    (net (code "138") (name "VCC_2") (class "Default")
      (node (ref "12V_TEST") (pin "1") (pinfunction "1_1") (pintype "passive"))
      (node (ref "C1") (pin "1") (pinfunction "1_1") (pintype "passive"))
      (node (ref "C11") (pin "1") (pinfunction "1_1") (pintype "passive"))
      (node (ref "C13") (pin "1") (pinfunction "1_1") (pintype "passive"))
      (node (ref "C15") (pin "1") (pinfunction "1_1") (pintype "passive"))
      (node (ref "C17") (pin "1") (pinfunction "1_1") (pintype "passive"))
      (node (ref "C19") (pin "1") (pinfunction "1_1") (pintype "passive"))
      (node (ref "C21") (pin "1") (pinfunction "1_1") (pintype "passive"))
      (node (ref "C23") (pin "1") (pinfunction "1_1") (pintype "passive"))
      (node (ref "C3") (pin "1") (pinfunction "1_1") (pintype "passive"))
      (node (ref "C5") (pin "1") (pinfunction "1_1") (pintype "passive"))
      (node (ref "C7") (pin "1") (pinfunction "1_1") (pintype "passive"))
      (node (ref "C9") (pin "1") (pinfunction "1_1") (pintype "passive"))
      (node (ref "D10") (pin "P$1") (pinfunction "P$1_P$1") (pintype "bidirectional"))
      (node (ref "D11") (pin "P$1") (pinfunction "P$1_P$1") (pintype "bidirectional"))
      (node (ref "D12") (pin "P$1") (pinfunction "P$1_P$1") (pintype "bidirectional"))
      (node (ref "D13") (pin "P$1") (pinfunction "P$1_P$1") (pintype "bidirectional"))
      (node (ref "D14") (pin "P$1") (pinfunction "P$1_P$1") (pintype "bidirectional"))
      (node (ref "D3") (pin "P$1") (pinfunction "P$1_P$1") (pintype "bidirectional"))
      (node (ref "D4") (pin "P$1") (pinfunction "P$1_P$1") (pintype "bidirectional"))
      (node (ref "D5") (pin "P$1") (pinfunction "P$1_P$1") (pintype "bidirectional"))
      (node (ref "D6") (pin "P$1") (pinfunction "P$1_P$1") (pintype "bidirectional"))
      (node (ref "D7") (pin "P$1") (pinfunction "P$1_P$1") (pintype "bidirectional"))
      (node (ref "D8") (pin "P$1") (pinfunction "P$1_P$1") (pintype "bidirectional"))
      (node (ref "D9") (pin "P$1") (pinfunction "P$1_P$1") (pintype "bidirectional"))
      (node (ref "DRIV1") (pin "1") (pinfunction "VCC_1") (pintype "bidirectional"))
      (node (ref "DRIV10") (pin "1") (pinfunction "VCC_1") (pintype "bidirectional"))
      (node (ref "DRIV11") (pin "1") (pinfunction "VCC_1") (pintype "bidirectional"))
      (node (ref "DRIV12") (pin "1") (pinfunction "VCC_1") (pintype "bidirectional"))
      (node (ref "DRIV2") (pin "1") (pinfunction "VCC_1") (pintype "bidirectional"))
      (node (ref "DRIV3") (pin "1") (pinfunction "VCC_1") (pintype "bidirectional"))
      (node (ref "DRIV4") (pin "1") (pinfunction "VCC_1") (pintype "bidirectional"))
      (node (ref "DRIV5") (pin "1") (pinfunction "VCC_1") (pintype "bidirectional"))
      (node (ref "DRIV6") (pin "1") (pinfunction "VCC_1") (pintype "bidirectional"))
      (node (ref "DRIV7") (pin "1") (pinfunction "VCC_1") (pintype "bidirectional"))
      (node (ref "DRIV8") (pin "1") (pinfunction "VCC_1") (pintype "bidirectional"))
      (node (ref "DRIV9") (pin "1") (pinfunction "VCC_1") (pintype "bidirectional"))
      (node (ref "MOS1") (pin "3") (pinfunction "SOURCE_3") (pintype "bidirectional"))
      (node (ref "MOS11") (pin "3") (pinfunction "SOURCE_3") (pintype "bidirectional"))
      (node (ref "MOS13") (pin "3") (pinfunction "SOURCE_3") (pintype "bidirectional"))
      (node (ref "MOS15") (pin "3") (pinfunction "SOURCE_3") (pintype "bidirectional"))
      (node (ref "MOS17") (pin "3") (pinfunction "SOURCE_3") (pintype "bidirectional"))
      (node (ref "MOS19") (pin "3") (pinfunction "SOURCE_3") (pintype "bidirectional"))
      (node (ref "MOS21") (pin "3") (pinfunction "SOURCE_3") (pintype "bidirectional"))
      (node (ref "MOS23") (pin "3") (pinfunction "SOURCE_3") (pintype "bidirectional"))
      (node (ref "MOS3") (pin "3") (pinfunction "SOURCE_3") (pintype "bidirectional"))
      (node (ref "MOS5") (pin "3") (pinfunction "SOURCE_3") (pintype "bidirectional"))
      (node (ref "MOS7") (pin "3") (pinfunction "SOURCE_3") (pintype "bidirectional"))
      (node (ref "MOS9") (pin "3") (pinfunction "SOURCE_3") (pintype "bidirectional"))
      (node (ref "POWER") (pin "12V@1") (pinfunction "12V_12V@1") (pintype "bidirectional"))
      (node (ref "POWER") (pin "12V@10") (pinfunction "12V_12V@10") (pintype "bidirectional"))
      (node (ref "POWER") (pin "12V@11") (pinfunction "12V_12V@11") (pintype "bidirectional"))
      (node (ref "POWER") (pin "12V@12") (pinfunction "12V_12V@12") (pintype "bidirectional"))
      (node (ref "POWER") (pin "12V@2") (pinfunction "12V_12V@2") (pintype "bidirectional"))
      (node (ref "POWER") (pin "12V@3") (pinfunction "12V_12V@3") (pintype "bidirectional"))
      (node (ref "POWER") (pin "12V@4") (pinfunction "12V_12V@4") (pintype "bidirectional"))
      (node (ref "POWER") (pin "12V@5") (pinfunction "12V_12V@5") (pintype "bidirectional"))
      (node (ref "POWER") (pin "12V@6") (pinfunction "12V_12V@6") (pintype "bidirectional"))
      (node (ref "POWER") (pin "12V@7") (pinfunction "12V_12V@7") (pintype "bidirectional"))
      (node (ref "POWER") (pin "12V@8") (pinfunction "12V_12V@8") (pintype "bidirectional"))
      (node (ref "POWER") (pin "12V@9") (pinfunction "12V_12V@9") (pintype "bidirectional"))
      (node (ref "R2") (pin "2") (pinfunction "2_2") (pintype "passive"))
    )
    (net (code "139") (name "unconnected-(STM1-PadPB7)") (class "Default")
      (node (ref "STM1") (pin "PB7") (pinfunction "PB7_PB7") (pintype "bidirectional"))
    )
    (net (code "140") (name "unconnected-(STM1-PadPF0-OSC_IN)") (class "Default")
      (node (ref "STM1") (pin "PF0-OSC_IN") (pinfunction "PF0-OSC_IN_PF0-OSC_IN") (pintype "bidirectional"))
    )
    (net (code "141") (name "unconnected-(STM1-PadPF1-OSC_OUT)") (class "Default")
      (node (ref "STM1") (pin "PF1-OSC_OUT") (pinfunction "PF1-OSC_OUT_PF1-OSC_OUT") (pintype "bidirectional"))
    )
    (net (code "142") (name "unconnected-(STM2-PadPB7)") (class "Default")
      (node (ref "STM2") (pin "PB7") (pinfunction "PB7_PB7") (pintype "bidirectional"))
    )
    (net (code "143") (name "unconnected-(STM2-PadPF0-OSC_IN)") (class "Default")
      (node (ref "STM2") (pin "PF0-OSC_IN") (pinfunction "PF0-OSC_IN_PF0-OSC_IN") (pintype "bidirectional"))
    )
    (net (code "144") (name "unconnected-(STM2-PadPF1-OSC_OUT)") (class "Default")
      (node (ref "STM2") (pin "PF1-OSC_OUT") (pinfunction "PF1-OSC_OUT_PF1-OSC_OUT") (pintype "bidirectional"))
    )
  )
)
